# PT08ttl2.net
KiCad netlist of a schematic drawn in EAGLE
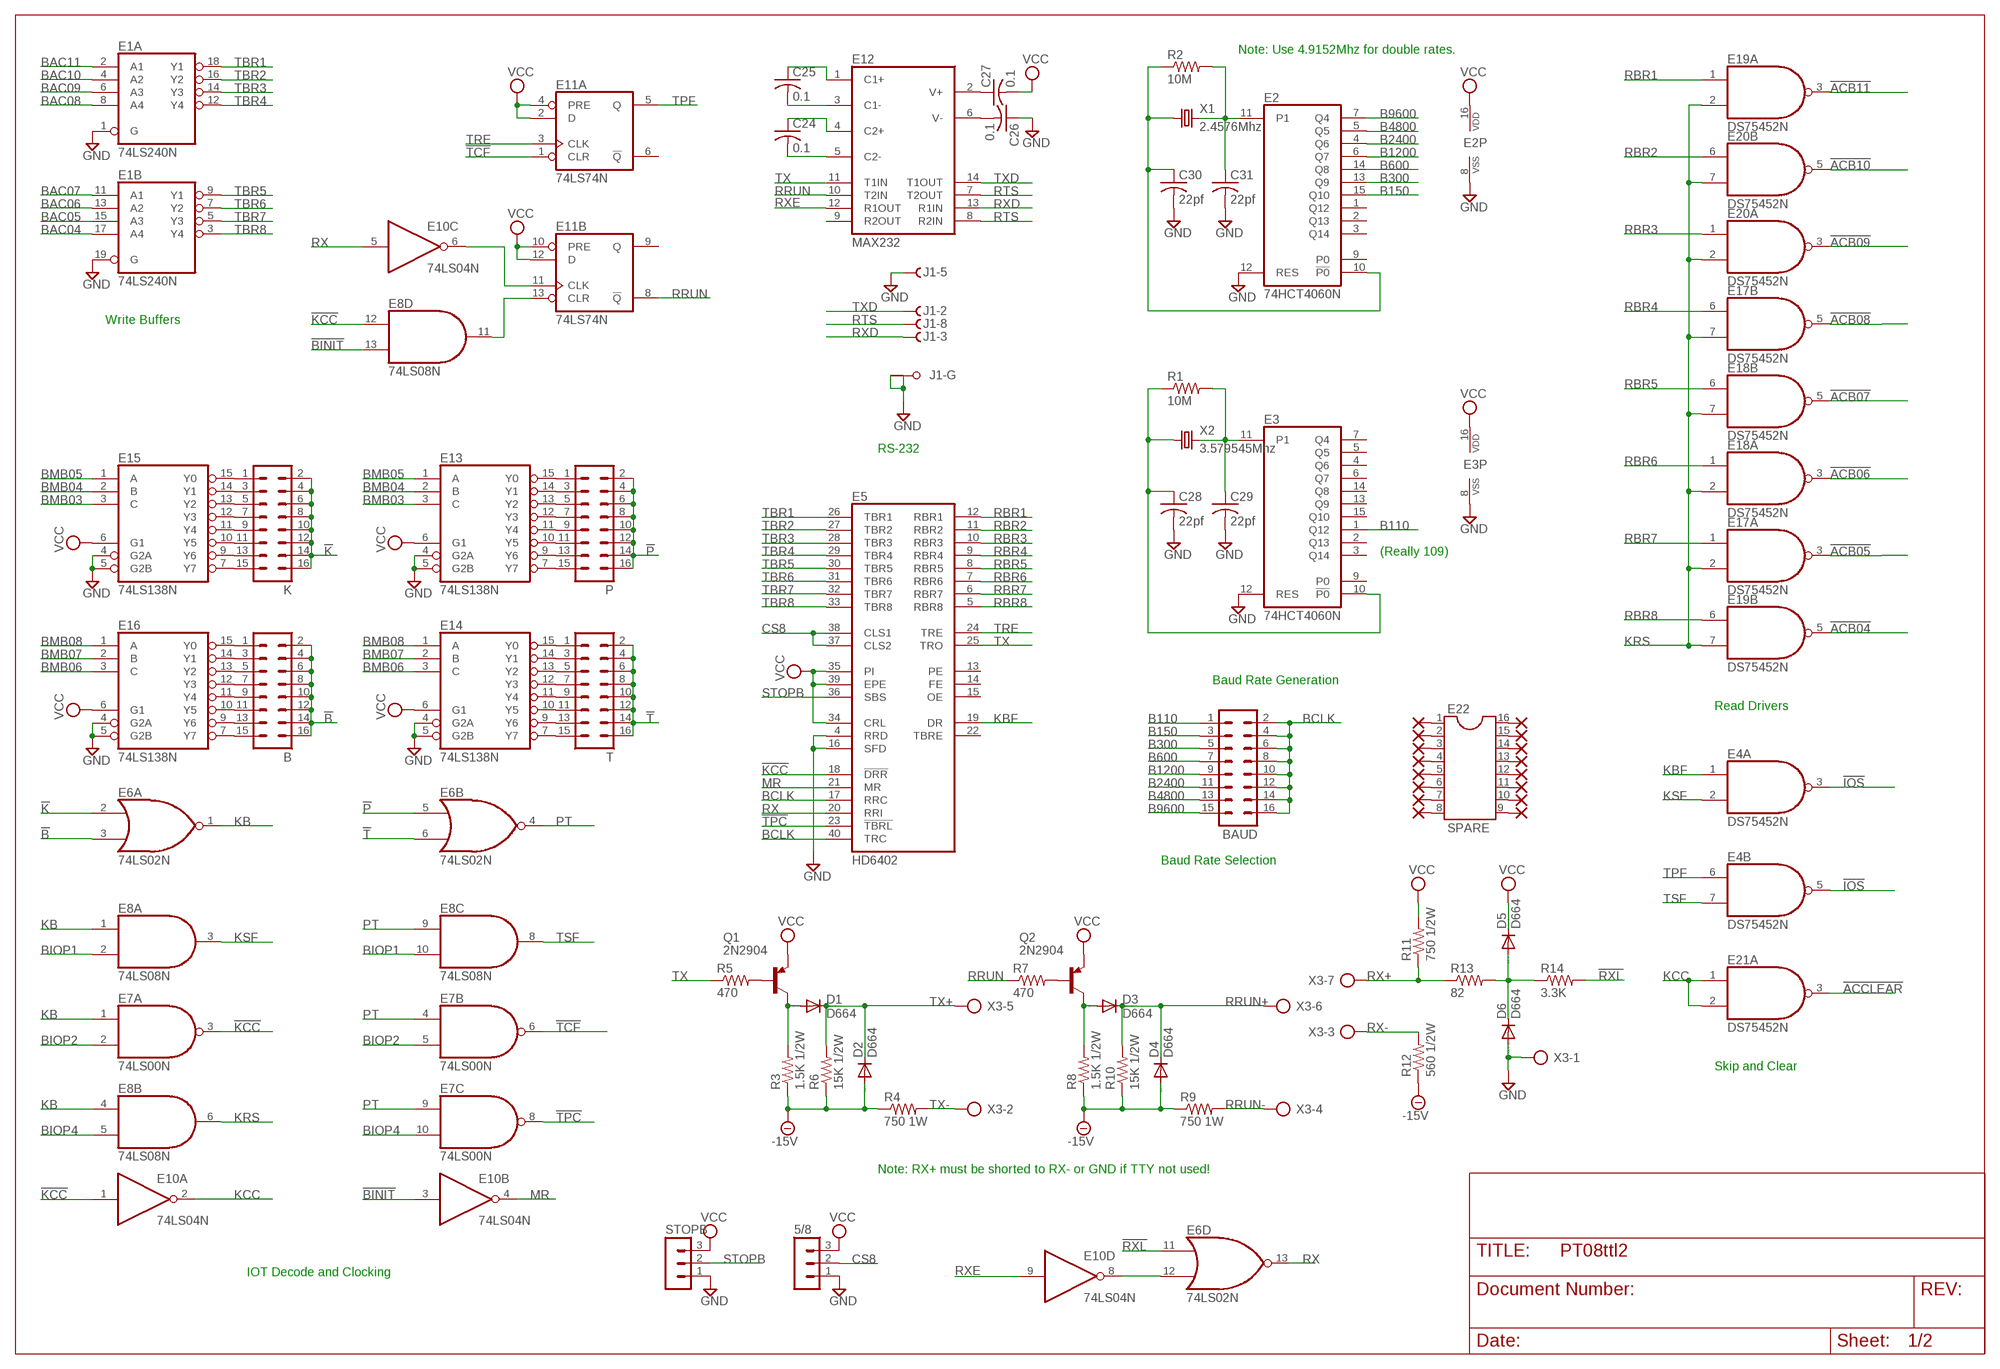
[diagram p0: schematic, sheet 1]
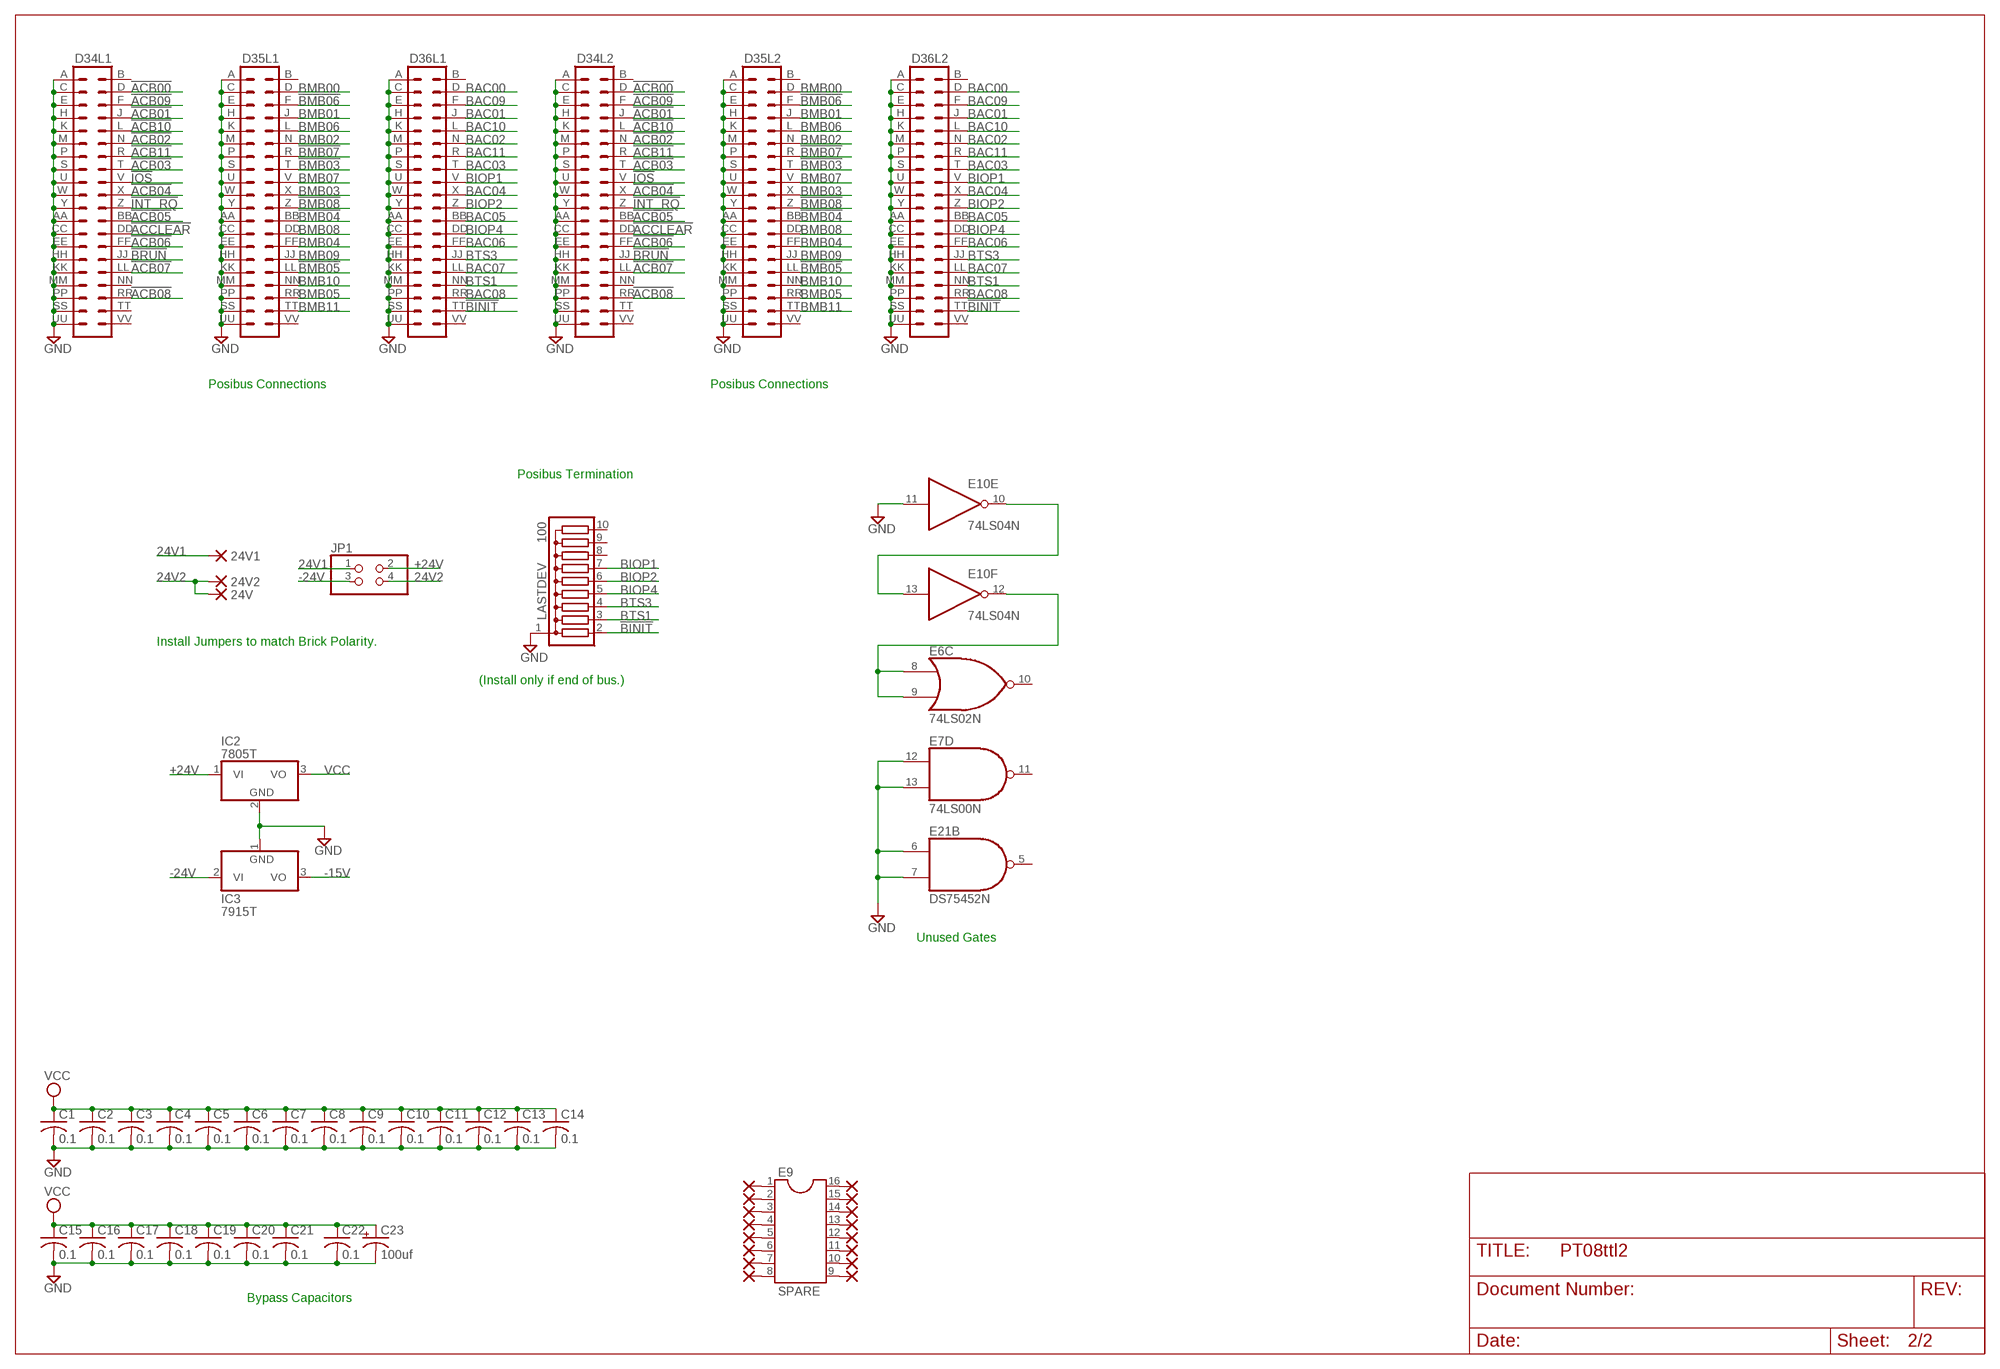
[diagram p1: schematic, sheet 2]

(export (version "E")
  (design (tool "Eeschema 10.0.6"))
  (components
    (comp (ref "5/8")
      (value "MA03-1")
      (footprint "eagle-import:MA03-1")
      (libsource (lib "eagle-import") (part "MA03-1"))
    )
    (comp (ref "B")
      (value "MA08-2")
      (footprint "eagle-import:MA08-2")
      (libsource (lib "eagle-import") (part "MA08-2"))
    )
    (comp (ref "BAUD")
      (value "MA08-2")
      (footprint "eagle-import:MA08-2")
      (libsource (lib "eagle-import") (part "MA08-2"))
    )
    (comp (ref "C24")
      (value "0.1")
      (footprint "eagle-import:C050-025X075")
      (libsource (lib "eagle-import") (part "C-US050-025X075"))
    )
    (comp (ref "C25")
      (value "0.1")
      (footprint "eagle-import:C050-025X075")
      (libsource (lib "eagle-import") (part "C-US050-025X075"))
    )
    (comp (ref "C26")
      (value "0.1")
      (footprint "eagle-import:C050-025X075")
      (libsource (lib "eagle-import") (part "C-US050-025X075"))
    )
    (comp (ref "C27")
      (value "0.1")
      (footprint "eagle-import:C050-025X075")
      (libsource (lib "eagle-import") (part "C-US050-025X075"))
    )
    (comp (ref "C28")
      (value "22pf")
      (footprint "eagle-import:C050-025X075")
      (libsource (lib "eagle-import") (part "C-US050-025X075"))
    )
    (comp (ref "C29")
      (value "22pf")
      (footprint "eagle-import:C050-025X075")
      (libsource (lib "eagle-import") (part "C-US050-025X075"))
    )
    (comp (ref "C30")
      (value "22pf")
      (footprint "eagle-import:C050-025X075")
      (libsource (lib "eagle-import") (part "C-US050-025X075"))
    )
    (comp (ref "C31")
      (value "22pf")
      (footprint "eagle-import:C050-025X075")
      (libsource (lib "eagle-import") (part "C-US050-025X075"))
    )
    (comp (ref "D1")
      (value "D664")
      (footprint "eagle-import:DO35-10")
      (libsource (lib "eagle-import") (part "1N4148DO35-10"))
    )
    (comp (ref "D2")
      (value "D664")
      (footprint "eagle-import:DO35-10")
      (libsource (lib "eagle-import") (part "1N4148DO35-10"))
    )
    (comp (ref "D3")
      (value "D664")
      (footprint "eagle-import:DO35-10")
      (libsource (lib "eagle-import") (part "1N4148DO35-10"))
    )
    (comp (ref "D4")
      (value "D664")
      (footprint "eagle-import:DO35-10")
      (libsource (lib "eagle-import") (part "1N4148DO35-10"))
    )
    (comp (ref "D5")
      (value "D664")
      (footprint "eagle-import:DO35-10")
      (libsource (lib "eagle-import") (part "1N4148DO35-10"))
    )
    (comp (ref "D6")
      (value "D664")
      (footprint "eagle-import:DO35-10")
      (libsource (lib "eagle-import") (part "1N4148DO35-10"))
    )
    (comp (ref "E1")
      (value "74LS240N")
      (footprint "eagle-import:DIL20")
      (libsource (lib "eagle-import") (part "74240NLS"))
    )
    (comp (ref "E2")
      (value "74HCT4060N")
      (footprint "eagle-import:DIL16")
      (libsource (lib "eagle-import") (part "4060N"))
    )
    (comp (ref "E3")
      (value "74HCT4060N")
      (footprint "eagle-import:DIL16")
      (libsource (lib "eagle-import") (part "4060N"))
    )
    (comp (ref "E4")
      (value "DS75452N")
      (footprint "eagle-import:DIL08")
      (libsource (lib "eagle-import") (part "DS75452N"))
    )
    (comp (ref "E5")
      (value "HD6402")
      (footprint "eagle-import:DIL40")
      (libsource (lib "eagle-import") (part "HD6402"))
    )
    (comp (ref "E6")
      (value "74LS02N")
      (footprint "eagle-import:DIL14")
      (libsource (lib "eagle-import") (part "7402NLS"))
    )
    (comp (ref "E7")
      (value "74LS00N")
      (footprint "eagle-import:DIL14")
      (libsource (lib "eagle-import") (part "7400NLS"))
    )
    (comp (ref "E8")
      (value "74LS08N")
      (footprint "eagle-import:DIL14")
      (libsource (lib "eagle-import") (part "7408NLS"))
    )
    (comp (ref "E10")
      (value "74LS04N")
      (footprint "eagle-import:DIL14")
      (libsource (lib "eagle-import") (part "7404NLS"))
    )
    (comp (ref "E11")
      (value "74LS74N")
      (footprint "eagle-import:DIL14")
      (libsource (lib "eagle-import") (part "7474NLS"))
    )
    (comp (ref "E12")
      (value "MAX232")
      (footprint "eagle-import:DIL16")
      (fields (field (name "MF") "MAXIM") (field (name "MPN") "MAX232ACPE+"))
      (libsource (lib "eagle-import") (part "MAX232"))
    )
    (comp (ref "E13")
      (value "74LS138N")
      (footprint "eagle-import:DIL16")
      (libsource (lib "eagle-import") (part "74138NLS"))
    )
    (comp (ref "E14")
      (value "74LS138N")
      (footprint "eagle-import:DIL16")
      (libsource (lib "eagle-import") (part "74138NLS"))
    )
    (comp (ref "E15")
      (value "74LS138N")
      (footprint "eagle-import:DIL16")
      (libsource (lib "eagle-import") (part "74138NLS"))
    )
    (comp (ref "E16")
      (value "74LS138N")
      (footprint "eagle-import:DIL16")
      (libsource (lib "eagle-import") (part "74138NLS"))
    )
    (comp (ref "E17")
      (value "DS75452N")
      (footprint "eagle-import:DIL08")
      (libsource (lib "eagle-import") (part "DS75452N"))
    )
    (comp (ref "E18")
      (value "DS75452N")
      (footprint "eagle-import:DIL08")
      (libsource (lib "eagle-import") (part "DS75452N"))
    )
    (comp (ref "E19")
      (value "DS75452N")
      (footprint "eagle-import:DIL08")
      (libsource (lib "eagle-import") (part "DS75452N"))
    )
    (comp (ref "E20")
      (value "DS75452N")
      (footprint "eagle-import:DIL08")
      (libsource (lib "eagle-import") (part "DS75452N"))
    )
    (comp (ref "E21")
      (value "DS75452N")
      (footprint "eagle-import:DIL08")
      (libsource (lib "eagle-import") (part "DS75452N"))
    )
    (comp (ref "E22")
      (value "SPARE")
      (footprint "eagle-import:DIL16")
      (libsource (lib "eagle-import") (part "DIL16"))
    )
    (comp (ref "J1")
      (value "F09HPS")
      (footprint "eagle-import:F09HP")
      (libsource (lib "eagle-import") (part "F09HPS"))
    )
    (comp (ref "K")
      (value "MA08-2")
      (footprint "eagle-import:MA08-2")
      (libsource (lib "eagle-import") (part "MA08-2"))
    )
    (comp (ref "P")
      (value "MA08-2")
      (footprint "eagle-import:MA08-2")
      (libsource (lib "eagle-import") (part "MA08-2"))
    )
    (comp (ref "PAD18")
      (value "1,6/0,8")
      (footprint "eagle-import:1,6_0,8")
      (libsource (lib "eagle-import") (part "1,6/0,8"))
    )
    (comp (ref "PAD19")
      (value "1,6/0,8")
      (footprint "eagle-import:1,6_0,8")
      (libsource (lib "eagle-import") (part "1,6/0,8"))
    )
    (comp (ref "PAD28")
      (value "1,6/0,8")
      (footprint "eagle-import:1,6_0,8")
      (libsource (lib "eagle-import") (part "1,6/0,8"))
    )
    (comp (ref "PAD29")
      (value "1,6/0,8")
      (footprint "eagle-import:1,6_0,8")
      (libsource (lib "eagle-import") (part "1,6/0,8"))
    )
    (comp (ref "PAD30")
      (value "1,6/0,8")
      (footprint "eagle-import:1,6_0,8")
      (libsource (lib "eagle-import") (part "1,6/0,8"))
    )
    (comp (ref "PAD31")
      (value "1,6/0,8")
      (footprint "eagle-import:1,6_0,8")
      (libsource (lib "eagle-import") (part "1,6/0,8"))
    )
    (comp (ref "PAD32")
      (value "1,6/0,8")
      (footprint "eagle-import:1,6_0,8")
      (libsource (lib "eagle-import") (part "1,6/0,8"))
    )
    (comp (ref "PAD33")
      (value "1,6/0,8")
      (footprint "eagle-import:1,6_0,8")
      (libsource (lib "eagle-import") (part "1,6/0,8"))
    )
    (comp (ref "PAD34")
      (value "1,6/0,8")
      (footprint "eagle-import:1,6_0,8")
      (libsource (lib "eagle-import") (part "1,6/0,8"))
    )
    (comp (ref "PAD35")
      (value "1,6/0,8")
      (footprint "eagle-import:1,6_0,8")
      (libsource (lib "eagle-import") (part "1,6/0,8"))
    )
    (comp (ref "PAD36")
      (value "1,6/0,8")
      (footprint "eagle-import:1,6_0,8")
      (libsource (lib "eagle-import") (part "1,6/0,8"))
    )
    (comp (ref "PAD37")
      (value "1,6/0,8")
      (footprint "eagle-import:1,6_0,8")
      (libsource (lib "eagle-import") (part "1,6/0,8"))
    )
    (comp (ref "PAD38")
      (value "1,6/0,8")
      (footprint "eagle-import:1,6_0,8")
      (libsource (lib "eagle-import") (part "1,6/0,8"))
    )
    (comp (ref "PAD39")
      (value "1,6/0,8")
      (footprint "eagle-import:1,6_0,8")
      (libsource (lib "eagle-import") (part "1,6/0,8"))
    )
    (comp (ref "PAD40")
      (value "1,6/0,8")
      (footprint "eagle-import:1,6_0,8")
      (libsource (lib "eagle-import") (part "1,6/0,8"))
    )
    (comp (ref "PAD41")
      (value "1,6/0,8")
      (footprint "eagle-import:1,6_0,8")
      (libsource (lib "eagle-import") (part "1,6/0,8"))
    )
    (comp (ref "Q1")
      (value "2N2904")
      (footprint "eagle-import:TO39")
      (libsource (lib "eagle-import") (part "2N2904"))
    )
    (comp (ref "Q2")
      (value "2N2904")
      (footprint "eagle-import:TO39")
      (libsource (lib "eagle-import") (part "2N2904"))
    )
    (comp (ref "R1")
      (value "10M")
      (footprint "eagle-import:0207_10")
      (libsource (lib "eagle-import") (part "R-US_0207/10"))
    )
    (comp (ref "R2")
      (value "10M")
      (footprint "eagle-import:0207_10")
      (libsource (lib "eagle-import") (part "R-US_0207/10"))
    )
    (comp (ref "R3")
      (value "1.5K 1/2W")
      (footprint "eagle-import:0207_10")
      (libsource (lib "eagle-import") (part "R-US_0207/10"))
    )
    (comp (ref "R4")
      (value "750 1W")
      (footprint "eagle-import:0207_10")
      (libsource (lib "eagle-import") (part "R-US_0207/10"))
    )
    (comp (ref "R5")
      (value "470")
      (footprint "eagle-import:0207_10")
      (libsource (lib "eagle-import") (part "R-US_0207/10"))
    )
    (comp (ref "R6")
      (value "15K 1/2W")
      (footprint "eagle-import:0207_10")
      (libsource (lib "eagle-import") (part "R-US_0207/10"))
    )
    (comp (ref "R7")
      (value "470")
      (footprint "eagle-import:0207_10")
      (libsource (lib "eagle-import") (part "R-US_0207/10"))
    )
    (comp (ref "R8")
      (value "1.5K 1/2W")
      (footprint "eagle-import:0207_10")
      (libsource (lib "eagle-import") (part "R-US_0207/10"))
    )
    (comp (ref "R9")
      (value "750 1W")
      (footprint "eagle-import:0207_10")
      (libsource (lib "eagle-import") (part "R-US_0207/10"))
    )
    (comp (ref "R10")
      (value "15K 1/2W")
      (footprint "eagle-import:0207_10")
      (libsource (lib "eagle-import") (part "R-US_0207/10"))
    )
    (comp (ref "R11")
      (value "750 1/2W")
      (footprint "eagle-import:0207_10")
      (libsource (lib "eagle-import") (part "R-US_0207/10"))
    )
    (comp (ref "R12")
      (value "560 1/2W")
      (footprint "eagle-import:0207_10")
      (libsource (lib "eagle-import") (part "R-US_0207/10"))
    )
    (comp (ref "R13")
      (value "82")
      (footprint "eagle-import:0207_10")
      (libsource (lib "eagle-import") (part "R-US_0207/10"))
    )
    (comp (ref "R14")
      (value "3.3K")
      (footprint "eagle-import:0207_10")
      (libsource (lib "eagle-import") (part "R-US_0207/10"))
    )
    (comp (ref "STOPB")
      (value "MA03-1")
      (footprint "eagle-import:MA03-1")
      (libsource (lib "eagle-import") (part "MA03-1"))
    )
    (comp (ref "T")
      (value "MA08-2")
      (footprint "eagle-import:MA08-2")
      (libsource (lib "eagle-import") (part "MA08-2"))
    )
    (comp (ref "X1")
      (value "2.4576Mhz")
      (footprint "eagle-import:HC49U-V")
      (libsource (lib "eagle-import") (part "CRYSTALHC49U-V"))
    )
    (comp (ref "X2")
      (value "3.579545Mhz")
      (footprint "eagle-import:HC49U-V")
      (libsource (lib "eagle-import") (part "CRYSTALHC49U-V"))
    )
    (comp (ref "X3")
      (value "AK300/7")
      (footprint "eagle-import:AK300_7")
      (libsource (lib "eagle-import") (part "AK300/7"))
    )
    (comp (ref "24V")
      (value "PAD-0820")
      (footprint "eagle-import:0820")
      (libsource (lib "eagle-import") (part "PAD-0820"))
    )
    (comp (ref "24V1")
      (value "PAD-0820")
      (footprint "eagle-import:0820")
      (libsource (lib "eagle-import") (part "PAD-0820"))
    )
    (comp (ref "24V2")
      (value "PAD-0820")
      (footprint "eagle-import:0820")
      (libsource (lib "eagle-import") (part "PAD-0820"))
    )
    (comp (ref "C1")
      (value "0.1")
      (footprint "eagle-import:C050-025X075")
      (libsource (lib "eagle-import") (part "C-US050-025X075"))
    )
    (comp (ref "C2")
      (value "0.1")
      (footprint "eagle-import:C050-025X075")
      (libsource (lib "eagle-import") (part "C-US050-025X075"))
    )
    (comp (ref "C3")
      (value "0.1")
      (footprint "eagle-import:C050-025X075")
      (libsource (lib "eagle-import") (part "C-US050-025X075"))
    )
    (comp (ref "C4")
      (value "0.1")
      (footprint "eagle-import:C050-025X075")
      (libsource (lib "eagle-import") (part "C-US050-025X075"))
    )
    (comp (ref "C5")
      (value "0.1")
      (footprint "eagle-import:C050-025X075")
      (libsource (lib "eagle-import") (part "C-US050-025X075"))
    )
    (comp (ref "C6")
      (value "0.1")
      (footprint "eagle-import:C050-025X075")
      (libsource (lib "eagle-import") (part "C-US050-025X075"))
    )
    (comp (ref "C7")
      (value "0.1")
      (footprint "eagle-import:C050-025X075")
      (libsource (lib "eagle-import") (part "C-US050-025X075"))
    )
    (comp (ref "C8")
      (value "0.1")
      (footprint "eagle-import:C050-025X075")
      (libsource (lib "eagle-import") (part "C-US050-025X075"))
    )
    (comp (ref "C9")
      (value "0.1")
      (footprint "eagle-import:C050-025X075")
      (libsource (lib "eagle-import") (part "C-US050-025X075"))
    )
    (comp (ref "C10")
      (value "0.1")
      (footprint "eagle-import:C050-025X075")
      (libsource (lib "eagle-import") (part "C-US050-025X075"))
    )
    (comp (ref "C11")
      (value "0.1")
      (footprint "eagle-import:C050-025X075")
      (libsource (lib "eagle-import") (part "C-US050-025X075"))
    )
    (comp (ref "C12")
      (value "0.1")
      (footprint "eagle-import:C050-025X075")
      (libsource (lib "eagle-import") (part "C-US050-025X075"))
    )
    (comp (ref "C13")
      (value "0.1")
      (footprint "eagle-import:C050-025X075")
      (libsource (lib "eagle-import") (part "C-US050-025X075"))
    )
    (comp (ref "C14")
      (value "0.1")
      (footprint "eagle-import:C050-025X075")
      (libsource (lib "eagle-import") (part "C-US050-025X075"))
    )
    (comp (ref "C15")
      (value "0.1")
      (footprint "eagle-import:C050-025X075")
      (libsource (lib "eagle-import") (part "C-US050-025X075"))
    )
    (comp (ref "C16")
      (value "0.1")
      (footprint "eagle-import:C050-025X075")
      (libsource (lib "eagle-import") (part "C-US050-025X075"))
    )
    (comp (ref "C17")
      (value "0.1")
      (footprint "eagle-import:C050-025X075")
      (libsource (lib "eagle-import") (part "C-US050-025X075"))
    )
    (comp (ref "C18")
      (value "0.1")
      (footprint "eagle-import:C050-025X075")
      (libsource (lib "eagle-import") (part "C-US050-025X075"))
    )
    (comp (ref "C19")
      (value "0.1")
      (footprint "eagle-import:C050-025X075")
      (libsource (lib "eagle-import") (part "C-US050-025X075"))
    )
    (comp (ref "C20")
      (value "0.1")
      (footprint "eagle-import:C050-025X075")
      (libsource (lib "eagle-import") (part "C-US050-025X075"))
    )
    (comp (ref "C21")
      (value "0.1")
      (footprint "eagle-import:C050-025X075")
      (libsource (lib "eagle-import") (part "C-US050-025X075"))
    )
    (comp (ref "C22")
      (value "0.1")
      (footprint "eagle-import:C050-025X075")
      (libsource (lib "eagle-import") (part "C-US050-025X075"))
    )
    (comp (ref "C23")
      (value "100uf")
      (footprint "eagle-import:E22-9")
      (libsource (lib "eagle-import") (part "CPOL-USE22-9AXIAL"))
    )
    (comp (ref "D34L1")
      (value "DEC40PINV")
      (footprint "eagle-import:DEC40PINV")
      (libsource (lib "eagle-import") (part "DEC40PINV"))
    )
    (comp (ref "D34L2")
      (value "DEC40PINV")
      (footprint "eagle-import:DEC40PINV")
      (libsource (lib "eagle-import") (part "DEC40PINV"))
    )
    (comp (ref "D35L1")
      (value "DEC40PINV")
      (footprint "eagle-import:DEC40PINV")
      (libsource (lib "eagle-import") (part "DEC40PINV"))
    )
    (comp (ref "D35L2")
      (value "DEC40PINV")
      (footprint "eagle-import:DEC40PINV")
      (libsource (lib "eagle-import") (part "DEC40PINV"))
    )
    (comp (ref "D36L1")
      (value "DEC40PINV")
      (footprint "eagle-import:DEC40PINV")
      (libsource (lib "eagle-import") (part "DEC40PINV"))
    )
    (comp (ref "D36L2")
      (value "DEC40PINV")
      (footprint "eagle-import:DEC40PINV")
      (libsource (lib "eagle-import") (part "DEC40PINV"))
    )
    (comp (ref "E9")
      (value "SPARE")
      (footprint "eagle-import:DIL16")
      (libsource (lib "eagle-import") (part "DIL16"))
    )
    (comp (ref "IC2")
      (value "7805T")
      (footprint "eagle-import:TO220H")
      (libsource (lib "eagle-import") (part "78T05"))
    )
    (comp (ref "IC3")
      (value "7915T")
      (footprint "eagle-import:TO220H")
      (libsource (lib "eagle-import") (part "79T15"))
    )
    (comp (ref "JP1")
      (value "PINHD-2X2")
      (footprint "eagle-import:2X02")
      (libsource (lib "eagle-import") (part "PINHD-2X2"))
    )
    (comp (ref "LASTDEV")
      (value "100")
      (footprint "eagle-import:SIL10")
      (libsource (lib "eagle-import") (part "G09R"))
    )
    (comp (ref "PAD1")
      (value "1,6/0,8")
      (footprint "eagle-import:1,6_0,8")
      (libsource (lib "eagle-import") (part "1,6/0,8"))
    )
    (comp (ref "PAD2")
      (value "1,6/0,8")
      (footprint "eagle-import:1,6_0,8")
      (libsource (lib "eagle-import") (part "1,6/0,8"))
    )
    (comp (ref "PAD3")
      (value "1,6/0,8")
      (footprint "eagle-import:1,6_0,8")
      (libsource (lib "eagle-import") (part "1,6/0,8"))
    )
    (comp (ref "PAD4")
      (value "1,6/0,8")
      (footprint "eagle-import:1,6_0,8")
      (libsource (lib "eagle-import") (part "1,6/0,8"))
    )
    (comp (ref "PAD5")
      (value "1,6/0,8")
      (footprint "eagle-import:1,6_0,8")
      (libsource (lib "eagle-import") (part "1,6/0,8"))
    )
    (comp (ref "PAD6")
      (value "1,6/0,8")
      (footprint "eagle-import:1,6_0,8")
      (libsource (lib "eagle-import") (part "1,6/0,8"))
    )
    (comp (ref "PAD7")
      (value "1,6/0,8")
      (footprint "eagle-import:1,6_0,8")
      (libsource (lib "eagle-import") (part "1,6/0,8"))
    )
    (comp (ref "PAD8")
      (value "1,6/0,8")
      (footprint "eagle-import:1,6_0,8")
      (libsource (lib "eagle-import") (part "1,6/0,8"))
    )
    (comp (ref "PAD9")
      (value "1,6/0,8")
      (footprint "eagle-import:1,6_0,8")
      (libsource (lib "eagle-import") (part "1,6/0,8"))
    )
    (comp (ref "PAD42")
      (value "1,6/0,8")
      (footprint "eagle-import:1,6_0,8")
      (libsource (lib "eagle-import") (part "1,6/0,8"))
    )
    (comp (ref "PAD43")
      (value "1,6/0,8")
      (footprint "eagle-import:1,6_0,8")
      (libsource (lib "eagle-import") (part "1,6/0,8"))
    )
    (comp (ref "PAD44")
      (value "1,6/0,8")
      (footprint "eagle-import:1,6_0,8")
      (libsource (lib "eagle-import") (part "1,6/0,8"))
    )
    (comp (ref "PAD45")
      (value "1,6/0,8")
      (footprint "eagle-import:1,6_0,8")
      (libsource (lib "eagle-import") (part "1,6/0,8"))
    )
    (comp (ref "PAD46")
      (value "1,6/0,8")
      (footprint "eagle-import:1,6_0,8")
      (libsource (lib "eagle-import") (part "1,6/0,8"))
    )
    (comp (ref "PAD47")
      (value "1,6/0,8")
      (footprint "eagle-import:1,6_0,8")
      (libsource (lib "eagle-import") (part "1,6/0,8"))
    )
    (comp (ref "PAD48")
      (value "1,6/0,8")
      (footprint "eagle-import:1,6_0,8")
      (libsource (lib "eagle-import") (part "1,6/0,8"))
    )
  )
  (nets
    (net (code "1") (name "+24V") (class "Default")
      (node (ref "IC2") (pin "1") (pinfunction "VI_1") (pintype "input"))
      (node (ref "JP1") (pin "2") (pinfunction "2_2") (pintype "passive"))
    )
    (net (code "2") (name "-15V") (class "Default")
      (node (ref "D2") (pin "A") (pinfunction "A_A") (pintype "passive"))
      (node (ref "D4") (pin "A") (pinfunction "A_A") (pintype "passive"))
      (node (ref "IC3") (pin "3") (pinfunction "VO_3") (pintype "passive"))
      (node (ref "R10") (pin "1") (pinfunction "1_1") (pintype "passive"))
      (node (ref "R12") (pin "1") (pinfunction "1_1") (pintype "passive"))
      (node (ref "R3") (pin "1") (pinfunction "1_1") (pintype "passive"))
      (node (ref "R4") (pin "1") (pinfunction "1_1") (pintype "passive"))
      (node (ref "R6") (pin "1") (pinfunction "1_1") (pintype "passive"))
      (node (ref "R8") (pin "1") (pinfunction "1_1") (pintype "passive"))
      (node (ref "R9") (pin "1") (pinfunction "1_1") (pintype "passive"))
    )
    (net (code "3") (name "-24V") (class "Default")
      (node (ref "IC3") (pin "2") (pinfunction "VI_2") (pintype "input"))
      (node (ref "JP1") (pin "3") (pinfunction "3_3") (pintype "passive"))
    )
    (net (code "4") (name "24V1") (class "Default")
      (node (ref "24V1") (pin "P$1") (pinfunction "P_P$1") (pintype "passive"))
      (node (ref "JP1") (pin "1") (pinfunction "1_1") (pintype "passive"))
    )
    (net (code "5") (name "24V2") (class "Default")
      (node (ref "24V") (pin "P$1") (pinfunction "P_P$1") (pintype "passive"))
      (node (ref "24V2") (pin "P$1") (pinfunction "P_P$1") (pintype "passive"))
      (node (ref "JP1") (pin "4") (pinfunction "4_4") (pintype "passive"))
    )
    (net (code "6") (name "B110") (class "Default")
      (node (ref "BAUD") (pin "1") (pinfunction "1_1") (pintype "passive"))
      (node (ref "E3") (pin "1") (pinfunction "Q12_1") (pintype "output"))
    )
    (net (code "7") (name "B150") (class "Default")
      (node (ref "BAUD") (pin "3") (pinfunction "3_3") (pintype "passive"))
      (node (ref "E2") (pin "15") (pinfunction "Q10_15") (pintype "output"))
    )
    (net (code "8") (name "B300") (class "Default")
      (node (ref "BAUD") (pin "5") (pinfunction "5_5") (pintype "passive"))
      (node (ref "E2") (pin "13") (pinfunction "Q9_13") (pintype "output"))
    )
    (net (code "9") (name "B600") (class "Default")
      (node (ref "BAUD") (pin "7") (pinfunction "7_7") (pintype "passive"))
      (node (ref "E2") (pin "14") (pinfunction "Q8_14") (pintype "output"))
    )
    (net (code "10") (name "B1200") (class "Default")
      (node (ref "BAUD") (pin "9") (pinfunction "9_9") (pintype "passive"))
      (node (ref "E2") (pin "6") (pinfunction "Q7_6") (pintype "output"))
    )
    (net (code "11") (name "B2400") (class "Default")
      (node (ref "BAUD") (pin "11") (pinfunction "11_11") (pintype "passive"))
      (node (ref "E2") (pin "4") (pinfunction "Q6_4") (pintype "output"))
    )
    (net (code "12") (name "B4800") (class "Default")
      (node (ref "BAUD") (pin "13") (pinfunction "13_13") (pintype "passive"))
      (node (ref "E2") (pin "5") (pinfunction "Q5_5") (pintype "output"))
    )
    (net (code "13") (name "B9600") (class "Default")
      (node (ref "BAUD") (pin "15") (pinfunction "15_15") (pintype "passive"))
      (node (ref "E2") (pin "7") (pinfunction "Q4_7") (pintype "output"))
    )
    (net (code "14") (name "BAC00") (class "Default")
      (node (ref "D36L1") (pin "D") (pinfunction "4_D") (pintype "bidirectional"))
      (node (ref "D36L2") (pin "D") (pinfunction "4_D") (pintype "bidirectional"))
    )
    (net (code "15") (name "BAC01") (class "Default")
      (node (ref "D36L1") (pin "J") (pinfunction "8_J") (pintype "bidirectional"))
      (node (ref "D36L2") (pin "J") (pinfunction "8_J") (pintype "bidirectional"))
    )
    (net (code "16") (name "BAC02") (class "Default")
      (node (ref "D36L1") (pin "N") (pinfunction "12_N") (pintype "bidirectional"))
      (node (ref "D36L2") (pin "N") (pinfunction "12_N") (pintype "bidirectional"))
    )
    (net (code "17") (name "BAC03") (class "Default")
      (node (ref "D36L1") (pin "T") (pinfunction "16_T") (pintype "bidirectional"))
      (node (ref "D36L2") (pin "T") (pinfunction "16_T") (pintype "bidirectional"))
    )
    (net (code "18") (name "BAC04") (class "Default")
      (node (ref "D36L1") (pin "X") (pinfunction "20_X") (pintype "bidirectional"))
      (node (ref "D36L2") (pin "X") (pinfunction "20_X") (pintype "bidirectional"))
      (node (ref "E1") (pin "17") (pinfunction "A4_17") (pintype "input"))
    )
    (net (code "19") (name "BAC05") (class "Default")
      (node (ref "D36L1") (pin "BB") (pinfunction "24_BB") (pintype "bidirectional"))
      (node (ref "D36L2") (pin "BB") (pinfunction "24_BB") (pintype "bidirectional"))
      (node (ref "E1") (pin "15") (pinfunction "A3_15") (pintype "input"))
    )
    (net (code "20") (name "BAC06") (class "Default")
      (node (ref "D36L1") (pin "FF") (pinfunction "28_FF") (pintype "bidirectional"))
      (node (ref "D36L2") (pin "FF") (pinfunction "28_FF") (pintype "bidirectional"))
      (node (ref "E1") (pin "13") (pinfunction "A2_13") (pintype "input"))
    )
    (net (code "21") (name "BAC07") (class "Default")
      (node (ref "D36L1") (pin "LL") (pinfunction "32_LL") (pintype "bidirectional"))
      (node (ref "D36L2") (pin "LL") (pinfunction "32_LL") (pintype "bidirectional"))
      (node (ref "E1") (pin "11") (pinfunction "A1_11") (pintype "input"))
    )
    (net (code "22") (name "BAC08") (class "Default")
      (node (ref "D36L1") (pin "RR") (pinfunction "36_RR") (pintype "bidirectional"))
      (node (ref "D36L2") (pin "RR") (pinfunction "36_RR") (pintype "bidirectional"))
      (node (ref "E1") (pin "8") (pinfunction "A4_8") (pintype "input"))
    )
    (net (code "23") (name "BAC09") (class "Default")
      (node (ref "D36L1") (pin "F") (pinfunction "6_F") (pintype "bidirectional"))
      (node (ref "D36L2") (pin "F") (pinfunction "6_F") (pintype "bidirectional"))
      (node (ref "E1") (pin "6") (pinfunction "A3_6") (pintype "input"))
    )
    (net (code "24") (name "BAC10") (class "Default")
      (node (ref "D36L1") (pin "L") (pinfunction "10_L") (pintype "bidirectional"))
      (node (ref "D36L2") (pin "L") (pinfunction "10_L") (pintype "bidirectional"))
      (node (ref "E1") (pin "4") (pinfunction "A2_4") (pintype "input"))
    )
    (net (code "25") (name "BAC11") (class "Default")
      (node (ref "D36L1") (pin "R") (pinfunction "14_R") (pintype "bidirectional"))
      (node (ref "D36L2") (pin "R") (pinfunction "14_R") (pintype "bidirectional"))
      (node (ref "E1") (pin "2") (pinfunction "A1_2") (pintype "input"))
    )
    (net (code "26") (name "BCLK") (class "Default")
      (node (ref "BAUD") (pin "10") (pinfunction "10_10") (pintype "passive"))
      (node (ref "BAUD") (pin "12") (pinfunction "12_12") (pintype "passive"))
      (node (ref "BAUD") (pin "14") (pinfunction "14_14") (pintype "passive"))
      (node (ref "BAUD") (pin "16") (pinfunction "16_16") (pintype "passive"))
      (node (ref "BAUD") (pin "2") (pinfunction "2_2") (pintype "passive"))
      (node (ref "BAUD") (pin "4") (pinfunction "4_4") (pintype "passive"))
      (node (ref "BAUD") (pin "6") (pinfunction "6_6") (pintype "passive"))
      (node (ref "BAUD") (pin "8") (pinfunction "8_8") (pintype "passive"))
      (node (ref "E5") (pin "17") (pinfunction "RRC_17") (pintype "input"))
      (node (ref "E5") (pin "40") (pinfunction "TRC_40") (pintype "input"))
    )
    (net (code "27") (name "BIOP1") (class "Default")
      (node (ref "D36L1") (pin "V") (pinfunction "18_V") (pintype "bidirectional"))
      (node (ref "D36L2") (pin "V") (pinfunction "18_V") (pintype "bidirectional"))
      (node (ref "E8") (pin "10") (pinfunction "I1_10") (pintype "input"))
      (node (ref "E8") (pin "2") (pinfunction "I1_2") (pintype "input"))
      (node (ref "LASTDEV") (pin "7") (pinfunction "7_7") (pintype "passive"))
    )
    (net (code "28") (name "BIOP2") (class "Default")
      (node (ref "D36L1") (pin "Z") (pinfunction "22_Z") (pintype "bidirectional"))
      (node (ref "D36L2") (pin "Z") (pinfunction "22_Z") (pintype "bidirectional"))
      (node (ref "E7") (pin "2") (pinfunction "I1_2") (pintype "input"))
      (node (ref "E7") (pin "5") (pinfunction "I1_5") (pintype "input"))
      (node (ref "LASTDEV") (pin "6") (pinfunction "6_6") (pintype "passive"))
    )
    (net (code "29") (name "BIOP4") (class "Default")
      (node (ref "D36L1") (pin "DD") (pinfunction "26_DD") (pintype "bidirectional"))
      (node (ref "D36L2") (pin "DD") (pinfunction "26_DD") (pintype "bidirectional"))
      (node (ref "E7") (pin "10") (pinfunction "I1_10") (pintype "input"))
      (node (ref "E8") (pin "5") (pinfunction "I1_5") (pintype "input"))
      (node (ref "LASTDEV") (pin "5") (pinfunction "5_5") (pintype "passive"))
    )
    (net (code "30") (name "BMB00") (class "Default")
      (node (ref "D35L1") (pin "D") (pinfunction "4_D") (pintype "bidirectional"))
      (node (ref "D35L2") (pin "D") (pinfunction "4_D") (pintype "bidirectional"))
    )
    (net (code "31") (name "BMB01") (class "Default")
      (node (ref "D35L1") (pin "J") (pinfunction "8_J") (pintype "bidirectional"))
      (node (ref "D35L2") (pin "J") (pinfunction "8_J") (pintype "bidirectional"))
    )
    (net (code "32") (name "BMB02") (class "Default")
      (node (ref "D35L1") (pin "N") (pinfunction "12_N") (pintype "bidirectional"))
      (node (ref "D35L2") (pin "N") (pinfunction "12_N") (pintype "bidirectional"))
    )
    (net (code "33") (name "BMB03") (class "Default")
      (node (ref "D35L1") (pin "X") (pinfunction "20_X") (pintype "bidirectional"))
      (node (ref "D35L2") (pin "X") (pinfunction "20_X") (pintype "bidirectional"))
      (node (ref "E13") (pin "3") (pinfunction "C_3") (pintype "input"))
      (node (ref "E15") (pin "3") (pinfunction "C_3") (pintype "input"))
    )
    (net (code "34") (name "BMB04") (class "Default")
      (node (ref "D35L1") (pin "FF") (pinfunction "28_FF") (pintype "bidirectional"))
      (node (ref "D35L2") (pin "FF") (pinfunction "28_FF") (pintype "bidirectional"))
      (node (ref "E13") (pin "2") (pinfunction "B_2") (pintype "input"))
      (node (ref "E15") (pin "2") (pinfunction "B_2") (pintype "input"))
    )
    (net (code "35") (name "BMB05") (class "Default")
      (node (ref "D35L1") (pin "RR") (pinfunction "36_RR") (pintype "bidirectional"))
      (node (ref "D35L2") (pin "RR") (pinfunction "36_RR") (pintype "bidirectional"))
      (node (ref "E13") (pin "1") (pinfunction "A_1") (pintype "input"))
      (node (ref "E15") (pin "1") (pinfunction "A_1") (pintype "input"))
    )
    (net (code "36") (name "BMB06") (class "Default")
      (node (ref "D35L1") (pin "L") (pinfunction "10_L") (pintype "bidirectional"))
      (node (ref "D35L2") (pin "L") (pinfunction "10_L") (pintype "bidirectional"))
      (node (ref "E14") (pin "3") (pinfunction "C_3") (pintype "input"))
      (node (ref "E16") (pin "3") (pinfunction "C_3") (pintype "input"))
    )
    (net (code "37") (name "BMB07") (class "Default")
      (node (ref "D35L1") (pin "V") (pinfunction "18_V") (pintype "bidirectional"))
      (node (ref "D35L2") (pin "V") (pinfunction "18_V") (pintype "bidirectional"))
      (node (ref "E14") (pin "2") (pinfunction "B_2") (pintype "input"))
      (node (ref "E16") (pin "2") (pinfunction "B_2") (pintype "input"))
    )
    (net (code "38") (name "BMB08") (class "Default")
      (node (ref "D35L1") (pin "DD") (pinfunction "26_DD") (pintype "bidirectional"))
      (node (ref "D35L2") (pin "DD") (pinfunction "26_DD") (pintype "bidirectional"))
      (node (ref "E14") (pin "1") (pinfunction "A_1") (pintype "input"))
      (node (ref "E16") (pin "1") (pinfunction "A_1") (pintype "input"))
    )
    (net (code "39") (name "BMB09") (class "Default")
      (node (ref "D35L1") (pin "JJ") (pinfunction "30_JJ") (pintype "bidirectional"))
      (node (ref "D35L2") (pin "JJ") (pinfunction "30_JJ") (pintype "bidirectional"))
    )
    (net (code "40") (name "BMB10") (class "Default")
      (node (ref "D35L1") (pin "NN") (pinfunction "34_NN") (pintype "bidirectional"))
      (node (ref "D35L2") (pin "NN") (pinfunction "34_NN") (pintype "bidirectional"))
    )
    (net (code "41") (name "BMB11") (class "Default")
      (node (ref "D35L1") (pin "TT") (pinfunction "38_TT") (pintype "bidirectional"))
      (node (ref "D35L2") (pin "TT") (pinfunction "38_TT") (pintype "bidirectional"))
    )
    (net (code "42") (name "BTS1") (class "Default")
      (node (ref "D36L1") (pin "NN") (pinfunction "34_NN") (pintype "bidirectional"))
      (node (ref "D36L2") (pin "NN") (pinfunction "34_NN") (pintype "bidirectional"))
      (node (ref "LASTDEV") (pin "3") (pinfunction "3_3") (pintype "passive"))
    )
    (net (code "43") (name "BTS3") (class "Default")
      (node (ref "D36L1") (pin "JJ") (pinfunction "30_JJ") (pintype "bidirectional"))
      (node (ref "D36L2") (pin "JJ") (pinfunction "30_JJ") (pintype "bidirectional"))
      (node (ref "LASTDEV") (pin "4") (pinfunction "4_4") (pintype "passive"))
    )
    (net (code "44") (name "CS8") (class "Default")
      (node (ref "5/8") (pin "2") (pinfunction "2_2") (pintype "passive"))
      (node (ref "E5") (pin "37") (pinfunction "CLS2_37") (pintype "input"))
      (node (ref "E5") (pin "38") (pinfunction "CLS1_38") (pintype "input"))
    )
    (net (code "45") (name "GND") (class "Default")
      (node (ref "5/8") (pin "1") (pinfunction "1_1") (pintype "passive"))
      (node (ref "C1") (pin "2") (pinfunction "2_2") (pintype "passive"))
      (node (ref "C10") (pin "2") (pinfunction "2_2") (pintype "passive"))
      (node (ref "C11") (pin "2") (pinfunction "2_2") (pintype "passive"))
      (node (ref "C12") (pin "2") (pinfunction "2_2") (pintype "passive"))
      (node (ref "C13") (pin "2") (pinfunction "2_2") (pintype "passive"))
      (node (ref "C14") (pin "2") (pinfunction "2_2") (pintype "passive"))
      (node (ref "C15") (pin "2") (pinfunction "2_2") (pintype "passive"))
      (node (ref "C16") (pin "2") (pinfunction "2_2") (pintype "passive"))
      (node (ref "C17") (pin "2") (pinfunction "2_2") (pintype "passive"))
      (node (ref "C18") (pin "2") (pinfunction "2_2") (pintype "passive"))
      (node (ref "C19") (pin "2") (pinfunction "2_2") (pintype "passive"))
      (node (ref "C2") (pin "2") (pinfunction "2_2") (pintype "passive"))
      (node (ref "C20") (pin "2") (pinfunction "2_2") (pintype "passive"))
      (node (ref "C21") (pin "2") (pinfunction "2_2") (pintype "passive"))
      (node (ref "C22") (pin "2") (pinfunction "2_2") (pintype "passive"))
      (node (ref "C23") (pin "-") (pinfunction "-_-") (pintype "passive"))
      (node (ref "C26") (pin "1") (pinfunction "1_1") (pintype "passive"))
      (node (ref "C28") (pin "2") (pinfunction "2_2") (pintype "passive"))
      (node (ref "C29") (pin "2") (pinfunction "2_2") (pintype "passive"))
      (node (ref "C3") (pin "2") (pinfunction "2_2") (pintype "passive"))
      (node (ref "C30") (pin "2") (pinfunction "2_2") (pintype "passive"))
      (node (ref "C31") (pin "2") (pinfunction "2_2") (pintype "passive"))
      (node (ref "C4") (pin "2") (pinfunction "2_2") (pintype "passive"))
      (node (ref "C5") (pin "2") (pinfunction "2_2") (pintype "passive"))
      (node (ref "C6") (pin "2") (pinfunction "2_2") (pintype "passive"))
      (node (ref "C7") (pin "2") (pinfunction "2_2") (pintype "passive"))
      (node (ref "C8") (pin "2") (pinfunction "2_2") (pintype "passive"))
      (node (ref "C9") (pin "2") (pinfunction "2_2") (pintype "passive"))
      (node (ref "D34L1") (pin "A") (pinfunction "1_A") (pintype "bidirectional"))
      (node (ref "D34L1") (pin "AA") (pinfunction "23_AA") (pintype "bidirectional"))
      (node (ref "D34L1") (pin "C") (pinfunction "3_C") (pintype "bidirectional"))
      (node (ref "D34L1") (pin "CC") (pinfunction "25_CC") (pintype "bidirectional"))
      (node (ref "D34L1") (pin "E") (pinfunction "5_E") (pintype "bidirectional"))
      (node (ref "D34L1") (pin "EE") (pinfunction "27_EE") (pintype "bidirectional"))
      (node (ref "D34L1") (pin "H") (pinfunction "7_H") (pintype "bidirectional"))
      (node (ref "D34L1") (pin "HH") (pinfunction "29_HH") (pintype "bidirectional"))
      (node (ref "D34L1") (pin "K") (pinfunction "9_K") (pintype "bidirectional"))
      (node (ref "D34L1") (pin "KK") (pinfunction "31_KK") (pintype "bidirectional"))
      (node (ref "D34L1") (pin "M") (pinfunction "11_M") (pintype "bidirectional"))
      (node (ref "D34L1") (pin "MM") (pinfunction "33_MM") (pintype "bidirectional"))
      (node (ref "D34L1") (pin "P") (pinfunction "13_P") (pintype "bidirectional"))
      (node (ref "D34L1") (pin "PP") (pinfunction "35_PP") (pintype "bidirectional"))
      (node (ref "D34L1") (pin "S") (pinfunction "15_S") (pintype "bidirectional"))
      (node (ref "D34L1") (pin "SS") (pinfunction "37_SS") (pintype "bidirectional"))
      (node (ref "D34L1") (pin "U") (pinfunction "17_U") (pintype "bidirectional"))
      (node (ref "D34L1") (pin "UU") (pinfunction "39_UU") (pintype "bidirectional"))
      (node (ref "D34L1") (pin "W") (pinfunction "19_W") (pintype "bidirectional"))
      (node (ref "D34L1") (pin "Y") (pinfunction "21_Y") (pintype "bidirectional"))
      (node (ref "D34L2") (pin "A") (pinfunction "1_A") (pintype "bidirectional"))
      (node (ref "D34L2") (pin "AA") (pinfunction "23_AA") (pintype "bidirectional"))
      (node (ref "D34L2") (pin "C") (pinfunction "3_C") (pintype "bidirectional"))
      (node (ref "D34L2") (pin "CC") (pinfunction "25_CC") (pintype "bidirectional"))
      (node (ref "D34L2") (pin "E") (pinfunction "5_E") (pintype "bidirectional"))
      (node (ref "D34L2") (pin "EE") (pinfunction "27_EE") (pintype "bidirectional"))
      (node (ref "D34L2") (pin "H") (pinfunction "7_H") (pintype "bidirectional"))
      (node (ref "D34L2") (pin "HH") (pinfunction "29_HH") (pintype "bidirectional"))
      (node (ref "D34L2") (pin "K") (pinfunction "9_K") (pintype "bidirectional"))
      (node (ref "D34L2") (pin "KK") (pinfunction "31_KK") (pintype "bidirectional"))
      (node (ref "D34L2") (pin "M") (pinfunction "11_M") (pintype "bidirectional"))
      (node (ref "D34L2") (pin "MM") (pinfunction "33_MM") (pintype "bidirectional"))
      (node (ref "D34L2") (pin "P") (pinfunction "13_P") (pintype "bidirectional"))
      (node (ref "D34L2") (pin "PP") (pinfunction "35_PP") (pintype "bidirectional"))
      (node (ref "D34L2") (pin "S") (pinfunction "15_S") (pintype "bidirectional"))
      (node (ref "D34L2") (pin "SS") (pinfunction "37_SS") (pintype "bidirectional"))
      (node (ref "D34L2") (pin "U") (pinfunction "17_U") (pintype "bidirectional"))
      (node (ref "D34L2") (pin "UU") (pinfunction "39_UU") (pintype "bidirectional"))
      (node (ref "D34L2") (pin "W") (pinfunction "19_W") (pintype "bidirectional"))
      (node (ref "D34L2") (pin "Y") (pinfunction "21_Y") (pintype "bidirectional"))
      (node (ref "D35L1") (pin "A") (pinfunction "1_A") (pintype "bidirectional"))
      (node (ref "D35L1") (pin "AA") (pinfunction "23_AA") (pintype "bidirectional"))
      (node (ref "D35L1") (pin "C") (pinfunction "3_C") (pintype "bidirectional"))
      (node (ref "D35L1") (pin "CC") (pinfunction "25_CC") (pintype "bidirectional"))
      (node (ref "D35L1") (pin "E") (pinfunction "5_E") (pintype "bidirectional"))
      (node (ref "D35L1") (pin "EE") (pinfunction "27_EE") (pintype "bidirectional"))
      (node (ref "D35L1") (pin "H") (pinfunction "7_H") (pintype "bidirectional"))
      (node (ref "D35L1") (pin "HH") (pinfunction "29_HH") (pintype "bidirectional"))
      (node (ref "D35L1") (pin "K") (pinfunction "9_K") (pintype "bidirectional"))
      (node (ref "D35L1") (pin "KK") (pinfunction "31_KK") (pintype "bidirectional"))
      (node (ref "D35L1") (pin "M") (pinfunction "11_M") (pintype "bidirectional"))
      (node (ref "D35L1") (pin "MM") (pinfunction "33_MM") (pintype "bidirectional"))
      (node (ref "D35L1") (pin "P") (pinfunction "13_P") (pintype "bidirectional"))
      (node (ref "D35L1") (pin "PP") (pinfunction "35_PP") (pintype "bidirectional"))
      (node (ref "D35L1") (pin "S") (pinfunction "15_S") (pintype "bidirectional"))
      (node (ref "D35L1") (pin "SS") (pinfunction "37_SS") (pintype "bidirectional"))
      (node (ref "D35L1") (pin "U") (pinfunction "17_U") (pintype "bidirectional"))
      (node (ref "D35L1") (pin "UU") (pinfunction "39_UU") (pintype "bidirectional"))
      (node (ref "D35L1") (pin "W") (pinfunction "19_W") (pintype "bidirectional"))
      (node (ref "D35L1") (pin "Y") (pinfunction "21_Y") (pintype "bidirectional"))
      (node (ref "D35L2") (pin "A") (pinfunction "1_A") (pintype "bidirectional"))
      (node (ref "D35L2") (pin "AA") (pinfunction "23_AA") (pintype "bidirectional"))
      (node (ref "D35L2") (pin "C") (pinfunction "3_C") (pintype "bidirectional"))
      (node (ref "D35L2") (pin "CC") (pinfunction "25_CC") (pintype "bidirectional"))
      (node (ref "D35L2") (pin "E") (pinfunction "5_E") (pintype "bidirectional"))
      (node (ref "D35L2") (pin "EE") (pinfunction "27_EE") (pintype "bidirectional"))
      (node (ref "D35L2") (pin "H") (pinfunction "7_H") (pintype "bidirectional"))
      (node (ref "D35L2") (pin "HH") (pinfunction "29_HH") (pintype "bidirectional"))
      (node (ref "D35L2") (pin "K") (pinfunction "9_K") (pintype "bidirectional"))
      (node (ref "D35L2") (pin "KK") (pinfunction "31_KK") (pintype "bidirectional"))
      (node (ref "D35L2") (pin "M") (pinfunction "11_M") (pintype "bidirectional"))
      (node (ref "D35L2") (pin "MM") (pinfunction "33_MM") (pintype "bidirectional"))
      (node (ref "D35L2") (pin "P") (pinfunction "13_P") (pintype "bidirectional"))
      (node (ref "D35L2") (pin "PP") (pinfunction "35_PP") (pintype "bidirectional"))
      (node (ref "D35L2") (pin "S") (pinfunction "15_S") (pintype "bidirectional"))
      (node (ref "D35L2") (pin "SS") (pinfunction "37_SS") (pintype "bidirectional"))
      (node (ref "D35L2") (pin "U") (pinfunction "17_U") (pintype "bidirectional"))
      (node (ref "D35L2") (pin "UU") (pinfunction "39_UU") (pintype "bidirectional"))
      (node (ref "D35L2") (pin "W") (pinfunction "19_W") (pintype "bidirectional"))
      (node (ref "D35L2") (pin "Y") (pinfunction "21_Y") (pintype "bidirectional"))
      (node (ref "D36L1") (pin "A") (pinfunction "1_A") (pintype "bidirectional"))
      (node (ref "D36L1") (pin "AA") (pinfunction "23_AA") (pintype "bidirectional"))
      (node (ref "D36L1") (pin "C") (pinfunction "3_C") (pintype "bidirectional"))
      (node (ref "D36L1") (pin "CC") (pinfunction "25_CC") (pintype "bidirectional"))
      (node (ref "D36L1") (pin "E") (pinfunction "5_E") (pintype "bidirectional"))
      (node (ref "D36L1") (pin "EE") (pinfunction "27_EE") (pintype "bidirectional"))
      (node (ref "D36L1") (pin "H") (pinfunction "7_H") (pintype "bidirectional"))
      (node (ref "D36L1") (pin "HH") (pinfunction "29_HH") (pintype "bidirectional"))
      (node (ref "D36L1") (pin "K") (pinfunction "9_K") (pintype "bidirectional"))
      (node (ref "D36L1") (pin "KK") (pinfunction "31_KK") (pintype "bidirectional"))
      (node (ref "D36L1") (pin "M") (pinfunction "11_M") (pintype "bidirectional"))
      (node (ref "D36L1") (pin "MM") (pinfunction "33_MM") (pintype "bidirectional"))
      (node (ref "D36L1") (pin "P") (pinfunction "13_P") (pintype "bidirectional"))
      (node (ref "D36L1") (pin "PP") (pinfunction "35_PP") (pintype "bidirectional"))
      (node (ref "D36L1") (pin "S") (pinfunction "15_S") (pintype "bidirectional"))
      (node (ref "D36L1") (pin "SS") (pinfunction "37_SS") (pintype "bidirectional"))
      (node (ref "D36L1") (pin "U") (pinfunction "17_U") (pintype "bidirectional"))
      (node (ref "D36L1") (pin "UU") (pinfunction "39_UU") (pintype "bidirectional"))
      (node (ref "D36L1") (pin "W") (pinfunction "19_W") (pintype "bidirectional"))
      (node (ref "D36L1") (pin "Y") (pinfunction "21_Y") (pintype "bidirectional"))
      (node (ref "D36L2") (pin "A") (pinfunction "1_A") (pintype "bidirectional"))
      (node (ref "D36L2") (pin "AA") (pinfunction "23_AA") (pintype "bidirectional"))
      (node (ref "D36L2") (pin "C") (pinfunction "3_C") (pintype "bidirectional"))
      (node (ref "D36L2") (pin "CC") (pinfunction "25_CC") (pintype "bidirectional"))
      (node (ref "D36L2") (pin "E") (pinfunction "5_E") (pintype "bidirectional"))
      (node (ref "D36L2") (pin "EE") (pinfunction "27_EE") (pintype "bidirectional"))
      (node (ref "D36L2") (pin "H") (pinfunction "7_H") (pintype "bidirectional"))
      (node (ref "D36L2") (pin "HH") (pinfunction "29_HH") (pintype "bidirectional"))
      (node (ref "D36L2") (pin "K") (pinfunction "9_K") (pintype "bidirectional"))
      (node (ref "D36L2") (pin "KK") (pinfunction "31_KK") (pintype "bidirectional"))
      (node (ref "D36L2") (pin "M") (pinfunction "11_M") (pintype "bidirectional"))
      (node (ref "D36L2") (pin "MM") (pinfunction "33_MM") (pintype "bidirectional"))
      (node (ref "D36L2") (pin "P") (pinfunction "13_P") (pintype "bidirectional"))
      (node (ref "D36L2") (pin "PP") (pinfunction "35_PP") (pintype "bidirectional"))
      (node (ref "D36L2") (pin "S") (pinfunction "15_S") (pintype "bidirectional"))
      (node (ref "D36L2") (pin "SS") (pinfunction "37_SS") (pintype "bidirectional"))
      (node (ref "D36L2") (pin "U") (pinfunction "17_U") (pintype "bidirectional"))
      (node (ref "D36L2") (pin "UU") (pinfunction "39_UU") (pintype "bidirectional"))
      (node (ref "D36L2") (pin "W") (pinfunction "19_W") (pintype "bidirectional"))
      (node (ref "D36L2") (pin "Y") (pinfunction "21_Y") (pintype "bidirectional"))
      (node (ref "D6") (pin "A") (pinfunction "A_A") (pintype "passive"))
      (node (ref "E1") (pin "1") (pinfunction "G_1") (pintype "input"))
      (node (ref "E1") (pin "19") (pinfunction "G_19") (pintype "input"))
      (node (ref "E10") (pin "11") (pinfunction "I_11") (pintype "input"))
      (node (ref "E13") (pin "4") (pinfunction "G2A_4") (pintype "input"))
      (node (ref "E13") (pin "5") (pinfunction "G2B_5") (pintype "input"))
      (node (ref "E14") (pin "4") (pinfunction "G2A_4") (pintype "input"))
      (node (ref "E14") (pin "5") (pinfunction "G2B_5") (pintype "input"))
      (node (ref "E15") (pin "4") (pinfunction "G2A_4") (pintype "input"))
      (node (ref "E15") (pin "5") (pinfunction "G2B_5") (pintype "input"))
      (node (ref "E16") (pin "4") (pinfunction "G2A_4") (pintype "input"))
      (node (ref "E16") (pin "5") (pinfunction "G2B_5") (pintype "input"))
      (node (ref "E2") (pin "12") (pinfunction "RES_12") (pintype "input"))
      (node (ref "E2") (pin "8") (pinfunction "VSS_8") (pintype "power_in"))
      (node (ref "E21") (pin "6") (pinfunction "I0_6") (pintype "input"))
      (node (ref "E21") (pin "7") (pinfunction "I1_7") (pintype "input"))
      (node (ref "E3") (pin "12") (pinfunction "RES_12") (pintype "input"))
      (node (ref "E3") (pin "8") (pinfunction "VSS_8") (pintype "power_in"))
      (node (ref "E5") (pin "16") (pinfunction "SFD_16") (pintype "input"))
      (node (ref "E5") (pin "4") (pinfunction "RRD_4") (pintype "input"))
      (node (ref "E7") (pin "12") (pinfunction "I0_12") (pintype "input"))
      (node (ref "E7") (pin "13") (pinfunction "I1_13") (pintype "input"))
      (node (ref "IC2") (pin "2") (pinfunction "GND_2") (pintype "passive"))
      (node (ref "IC3") (pin "1") (pinfunction "GND_1") (pintype "passive"))
      (node (ref "J1") (pin "5") (pinfunction "F_5") (pintype "passive"))
      (node (ref "J1") (pin "G1") (pinfunction "G1_G1") (pintype "passive"))
      (node (ref "J1") (pin "G2") (pinfunction "G2_G2") (pintype "passive"))
      (node (ref "LASTDEV") (pin "1") (pinfunction "1_1") (pintype "passive"))
      (node (ref "STOPB") (pin "1") (pinfunction "1_1") (pintype "passive"))
      (node (ref "X3") (pin "1") (pinfunction "KL_1") (pintype "passive"))
    )
    (net (code "46") (name "KB") (class "Default")
      (node (ref "E6") (pin "1") (pinfunction "O_1") (pintype "output"))
      (node (ref "E7") (pin "1") (pinfunction "I0_1") (pintype "input"))
      (node (ref "E8") (pin "1") (pinfunction "I0_1") (pintype "input"))
      (node (ref "E8") (pin "4") (pinfunction "I0_4") (pintype "input"))
    )
    (net (code "47") (name "KBF") (class "Default")
      (node (ref "E4") (pin "1") (pinfunction "I0_1") (pintype "input"))
      (node (ref "E5") (pin "19") (pinfunction "DR_19") (pintype "tri_state"))
    )
    (net (code "48") (name "KCC") (class "Default")
      (node (ref "E10") (pin "2") (pinfunction "O_2") (pintype "output"))
      (node (ref "E21") (pin "1") (pinfunction "I0_1") (pintype "input"))
      (node (ref "E21") (pin "2") (pinfunction "I1_2") (pintype "input"))
    )
    (net (code "49") (name "KRS") (class "Default")
      (node (ref "E17") (pin "2") (pinfunction "I1_2") (pintype "input"))
      (node (ref "E17") (pin "7") (pinfunction "I1_7") (pintype "input"))
      (node (ref "E18") (pin "2") (pinfunction "I1_2") (pintype "input"))
      (node (ref "E18") (pin "7") (pinfunction "I1_7") (pintype "input"))
      (node (ref "E19") (pin "2") (pinfunction "I1_2") (pintype "input"))
      (node (ref "E19") (pin "7") (pinfunction "I1_7") (pintype "input"))
      (node (ref "E20") (pin "2") (pinfunction "I1_2") (pintype "input"))
      (node (ref "E20") (pin "7") (pinfunction "I1_7") (pintype "input"))
      (node (ref "E8") (pin "6") (pinfunction "O_6") (pintype "output"))
    )
    (net (code "50") (name "KSF") (class "Default")
      (node (ref "E4") (pin "2") (pinfunction "I1_2") (pintype "input"))
      (node (ref "E8") (pin "3") (pinfunction "O_3") (pintype "output"))
    )
    (net (code "51") (name "MR") (class "Default")
      (node (ref "E10") (pin "4") (pinfunction "O_4") (pintype "output"))
      (node (ref "E5") (pin "21") (pinfunction "MR_21") (pintype "input"))
    )
    (net (code "52") (name "Net-(D5-PadA)") (class "Default")
      (node (ref "D5") (pin "A") (pinfunction "A_A") (pintype "passive"))
      (node (ref "D6") (pin "C") (pinfunction "C_C") (pintype "passive"))
      (node (ref "R13") (pin "2") (pinfunction "2_2") (pintype "passive"))
      (node (ref "R14") (pin "1") (pinfunction "1_1") (pintype "passive"))
    )
    (net (code "53") (name "Net-(E2A-P1)") (class "Default")
      (node (ref "C31") (pin "1") (pinfunction "1_1") (pintype "passive"))
      (node (ref "E2") (pin "11") (pinfunction "P1_11") (pintype "input"))
      (node (ref "R2") (pin "2") (pinfunction "2_2") (pintype "passive"))
      (node (ref "X1") (pin "2") (pinfunction "2_2") (pintype "passive"))
    )
    (net (code "54") (name "Net-(E2A-~{P0})") (class "Default")
      (node (ref "C30") (pin "1") (pinfunction "1_1") (pintype "passive"))
      (node (ref "E2") (pin "10") (pinfunction "~{P0}_10") (pintype "output"))
      (node (ref "R2") (pin "1") (pinfunction "1_1") (pintype "passive"))
      (node (ref "X1") (pin "1") (pinfunction "1_1") (pintype "passive"))
    )
    (net (code "55") (name "Net-(E3A-P1)") (class "Default")
      (node (ref "C29") (pin "1") (pinfunction "1_1") (pintype "passive"))
      (node (ref "E3") (pin "11") (pinfunction "P1_11") (pintype "input"))
      (node (ref "R1") (pin "2") (pinfunction "2_2") (pintype "passive"))
      (node (ref "X2") (pin "2") (pinfunction "2_2") (pintype "passive"))
    )
    (net (code "56") (name "Net-(E3A-~{P0})") (class "Default")
      (node (ref "C28") (pin "1") (pinfunction "1_1") (pintype "passive"))
      (node (ref "E3") (pin "10") (pinfunction "~{P0}_10") (pintype "output"))
      (node (ref "R1") (pin "1") (pinfunction "1_1") (pintype "passive"))
      (node (ref "X2") (pin "1") (pinfunction "1_1") (pintype "passive"))
    )
    (net (code "57") (name "Net-(E10C-O)") (class "Default")
      (node (ref "E10") (pin "6") (pinfunction "O_6") (pintype "output"))
      (node (ref "E11") (pin "11") (pinfunction "CLK_11") (pintype "input"))
    )
    (net (code "58") (name "Net-(E10D-O)") (class "Default")
      (node (ref "E10") (pin "8") (pinfunction "O_8") (pintype "output"))
      (node (ref "E6") (pin "12") (pinfunction "I1_12") (pintype "input"))
    )
    (net (code "59") (name "Net-(E10E-O)") (class "Default")
      (node (ref "E10") (pin "10") (pinfunction "O_10") (pintype "output"))
      (node (ref "E10") (pin "13") (pinfunction "I_13") (pintype "input"))
    )
    (net (code "60") (name "Net-(E10F-O)") (class "Default")
      (node (ref "E10") (pin "12") (pinfunction "O_12") (pintype "output"))
      (node (ref "E6") (pin "8") (pinfunction "I0_8") (pintype "input"))
      (node (ref "E6") (pin "9") (pinfunction "I1_9") (pintype "input"))
    )
    (net (code "61") (name "Net-(E11B-CLR)") (class "Default")
      (node (ref "E11") (pin "13") (pinfunction "CLR_13") (pintype "input"))
      (node (ref "E8") (pin "11") (pinfunction "O_11") (pintype "output"))
    )
    (net (code "62") (name "Net-(E12A-C1+)") (class "Default")
      (node (ref "C25") (pin "1") (pinfunction "1_1") (pintype "passive"))
      (node (ref "E12") (pin "1") (pinfunction "C1+_1") (pintype "bidirectional"))
    )
    (net (code "63") (name "Net-(E12A-C1-)") (class "Default")
      (node (ref "C25") (pin "2") (pinfunction "2_2") (pintype "passive"))
      (node (ref "E12") (pin "3") (pinfunction "C1-_3") (pintype "bidirectional"))
    )
    (net (code "64") (name "Net-(E12A-C2+)") (class "Default")
      (node (ref "C24") (pin "1") (pinfunction "1_1") (pintype "passive"))
      (node (ref "E12") (pin "4") (pinfunction "C2+_4") (pintype "bidirectional"))
    )
    (net (code "65") (name "Net-(E12A-C2-)") (class "Default")
      (node (ref "C24") (pin "2") (pinfunction "2_2") (pintype "passive"))
      (node (ref "E12") (pin "5") (pinfunction "C2-_5") (pintype "bidirectional"))
    )
    (net (code "66") (name "Net-(E12A-V+)") (class "Default")
      (node (ref "C27") (pin "1") (pinfunction "1_1") (pintype "passive"))
      (node (ref "E12") (pin "2") (pinfunction "V+_2") (pintype "bidirectional"))
    )
    (net (code "67") (name "Net-(E12A-V-)") (class "Default")
      (node (ref "C26") (pin "2") (pinfunction "2_2") (pintype "passive"))
      (node (ref "E12") (pin "6") (pinfunction "V-_6") (pintype "bidirectional"))
    )
    (net (code "68") (name "Net-(E13A-Y0)") (class "Default")
      (node (ref "E13") (pin "15") (pinfunction "Y0_15") (pintype "output"))
      (node (ref "P") (pin "1") (pinfunction "1_1") (pintype "passive"))
    )
    (net (code "69") (name "Net-(E13A-Y1)") (class "Default")
      (node (ref "E13") (pin "14") (pinfunction "Y1_14") (pintype "output"))
      (node (ref "P") (pin "3") (pinfunction "3_3") (pintype "passive"))
    )
    (net (code "70") (name "Net-(E13A-Y2)") (class "Default")
      (node (ref "E13") (pin "13") (pinfunction "Y2_13") (pintype "output"))
      (node (ref "P") (pin "5") (pinfunction "5_5") (pintype "passive"))
    )
    (net (code "71") (name "Net-(E13A-Y3)") (class "Default")
      (node (ref "E13") (pin "12") (pinfunction "Y3_12") (pintype "output"))
      (node (ref "P") (pin "7") (pinfunction "7_7") (pintype "passive"))
    )
    (net (code "72") (name "Net-(E13A-Y4)") (class "Default")
      (node (ref "E13") (pin "11") (pinfunction "Y4_11") (pintype "output"))
      (node (ref "P") (pin "9") (pinfunction "9_9") (pintype "passive"))
    )
    (net (code "73") (name "Net-(E13A-Y5)") (class "Default")
      (node (ref "E13") (pin "10") (pinfunction "Y5_10") (pintype "output"))
      (node (ref "P") (pin "11") (pinfunction "11_11") (pintype "passive"))
    )
    (net (code "74") (name "Net-(E13A-Y6)") (class "Default")
      (node (ref "E13") (pin "9") (pinfunction "Y6_9") (pintype "output"))
      (node (ref "P") (pin "13") (pinfunction "13_13") (pintype "passive"))
    )
    (net (code "75") (name "Net-(E13A-Y7)") (class "Default")
      (node (ref "E13") (pin "7") (pinfunction "Y7_7") (pintype "output"))
      (node (ref "P") (pin "15") (pinfunction "15_15") (pintype "passive"))
    )
    (net (code "76") (name "Net-(E14A-Y0)") (class "Default")
      (node (ref "E14") (pin "15") (pinfunction "Y0_15") (pintype "output"))
      (node (ref "T") (pin "1") (pinfunction "1_1") (pintype "passive"))
    )
    (net (code "77") (name "Net-(E14A-Y1)") (class "Default")
      (node (ref "E14") (pin "14") (pinfunction "Y1_14") (pintype "output"))
      (node (ref "T") (pin "3") (pinfunction "3_3") (pintype "passive"))
    )
    (net (code "78") (name "Net-(E14A-Y2)") (class "Default")
      (node (ref "E14") (pin "13") (pinfunction "Y2_13") (pintype "output"))
      (node (ref "T") (pin "5") (pinfunction "5_5") (pintype "passive"))
    )
    (net (code "79") (name "Net-(E14A-Y3)") (class "Default")
      (node (ref "E14") (pin "12") (pinfunction "Y3_12") (pintype "output"))
      (node (ref "T") (pin "7") (pinfunction "7_7") (pintype "passive"))
    )
    (net (code "80") (name "Net-(E14A-Y4)") (class "Default")
      (node (ref "E14") (pin "11") (pinfunction "Y4_11") (pintype "output"))
      (node (ref "T") (pin "9") (pinfunction "9_9") (pintype "passive"))
    )
    (net (code "81") (name "Net-(E14A-Y5)") (class "Default")
      (node (ref "E14") (pin "10") (pinfunction "Y5_10") (pintype "output"))
      (node (ref "T") (pin "11") (pinfunction "11_11") (pintype "passive"))
    )
    (net (code "82") (name "Net-(E14A-Y6)") (class "Default")
      (node (ref "E14") (pin "9") (pinfunction "Y6_9") (pintype "output"))
      (node (ref "T") (pin "13") (pinfunction "13_13") (pintype "passive"))
    )
    (net (code "83") (name "Net-(E14A-Y7)") (class "Default")
      (node (ref "E14") (pin "7") (pinfunction "Y7_7") (pintype "output"))
      (node (ref "T") (pin "15") (pinfunction "15_15") (pintype "passive"))
    )
    (net (code "84") (name "Net-(E15A-Y0)") (class "Default")
      (node (ref "E15") (pin "15") (pinfunction "Y0_15") (pintype "output"))
      (node (ref "K") (pin "1") (pinfunction "1_1") (pintype "passive"))
    )
    (net (code "85") (name "Net-(E15A-Y1)") (class "Default")
      (node (ref "E15") (pin "14") (pinfunction "Y1_14") (pintype "output"))
      (node (ref "K") (pin "3") (pinfunction "3_3") (pintype "passive"))
    )
    (net (code "86") (name "Net-(E15A-Y2)") (class "Default")
      (node (ref "E15") (pin "13") (pinfunction "Y2_13") (pintype "output"))
      (node (ref "K") (pin "5") (pinfunction "5_5") (pintype "passive"))
    )
    (net (code "87") (name "Net-(E15A-Y3)") (class "Default")
      (node (ref "E15") (pin "12") (pinfunction "Y3_12") (pintype "output"))
      (node (ref "K") (pin "7") (pinfunction "7_7") (pintype "passive"))
    )
    (net (code "88") (name "Net-(E15A-Y4)") (class "Default")
      (node (ref "E15") (pin "11") (pinfunction "Y4_11") (pintype "output"))
      (node (ref "K") (pin "9") (pinfunction "9_9") (pintype "passive"))
    )
    (net (code "89") (name "Net-(E15A-Y5)") (class "Default")
      (node (ref "E15") (pin "10") (pinfunction "Y5_10") (pintype "output"))
      (node (ref "K") (pin "11") (pinfunction "11_11") (pintype "passive"))
    )
    (net (code "90") (name "Net-(E15A-Y6)") (class "Default")
      (node (ref "E15") (pin "9") (pinfunction "Y6_9") (pintype "output"))
      (node (ref "K") (pin "13") (pinfunction "13_13") (pintype "passive"))
    )
    (net (code "91") (name "Net-(E15A-Y7)") (class "Default")
      (node (ref "E15") (pin "7") (pinfunction "Y7_7") (pintype "output"))
      (node (ref "K") (pin "15") (pinfunction "15_15") (pintype "passive"))
    )
    (net (code "92") (name "Net-(E16A-Y0)") (class "Default")
      (node (ref "B") (pin "1") (pinfunction "1_1") (pintype "passive"))
      (node (ref "E16") (pin "15") (pinfunction "Y0_15") (pintype "output"))
    )
    (net (code "93") (name "Net-(E16A-Y1)") (class "Default")
      (node (ref "B") (pin "3") (pinfunction "3_3") (pintype "passive"))
      (node (ref "E16") (pin "14") (pinfunction "Y1_14") (pintype "output"))
    )
    (net (code "94") (name "Net-(E16A-Y2)") (class "Default")
      (node (ref "B") (pin "5") (pinfunction "5_5") (pintype "passive"))
      (node (ref "E16") (pin "13") (pinfunction "Y2_13") (pintype "output"))
    )
    (net (code "95") (name "Net-(E16A-Y3)") (class "Default")
      (node (ref "B") (pin "7") (pinfunction "7_7") (pintype "passive"))
      (node (ref "E16") (pin "12") (pinfunction "Y3_12") (pintype "output"))
    )
    (net (code "96") (name "Net-(E16A-Y4)") (class "Default")
      (node (ref "B") (pin "9") (pinfunction "9_9") (pintype "passive"))
      (node (ref "E16") (pin "11") (pinfunction "Y4_11") (pintype "output"))
    )
    (net (code "97") (name "Net-(E16A-Y5)") (class "Default")
      (node (ref "B") (pin "11") (pinfunction "11_11") (pintype "passive"))
      (node (ref "E16") (pin "10") (pinfunction "Y5_10") (pintype "output"))
    )
    (net (code "98") (name "Net-(E16A-Y6)") (class "Default")
      (node (ref "B") (pin "13") (pinfunction "13_13") (pintype "passive"))
      (node (ref "E16") (pin "9") (pinfunction "Y6_9") (pintype "output"))
    )
    (net (code "99") (name "Net-(E16A-Y7)") (class "Default")
      (node (ref "B") (pin "15") (pinfunction "15_15") (pintype "passive"))
      (node (ref "E16") (pin "7") (pinfunction "Y7_7") (pintype "output"))
    )
    (net (code "100") (name "Net-(PAD1-P)") (class "Default")
      (node (ref "E9") (pin "1") (pinfunction "1_1") (pintype "passive"))
      (node (ref "PAD1") (pin "1") (pinfunction "P_1") (pintype "passive"))
    )
    (net (code "101") (name "Net-(PAD2-P)") (class "Default")
      (node (ref "E9") (pin "2") (pinfunction "2_2") (pintype "passive"))
      (node (ref "PAD2") (pin "1") (pinfunction "P_1") (pintype "passive"))
    )
    (net (code "102") (name "Net-(PAD3-P)") (class "Default")
      (node (ref "E9") (pin "3") (pinfunction "3_3") (pintype "passive"))
      (node (ref "PAD3") (pin "1") (pinfunction "P_1") (pintype "passive"))
    )
    (net (code "103") (name "Net-(PAD4-P)") (class "Default")
      (node (ref "E9") (pin "4") (pinfunction "4_4") (pintype "passive"))
      (node (ref "PAD4") (pin "1") (pinfunction "P_1") (pintype "passive"))
    )
    (net (code "104") (name "Net-(PAD5-P)") (class "Default")
      (node (ref "E9") (pin "5") (pinfunction "5_5") (pintype "passive"))
      (node (ref "PAD5") (pin "1") (pinfunction "P_1") (pintype "passive"))
    )
    (net (code "105") (name "Net-(PAD6-P)") (class "Default")
      (node (ref "E9") (pin "6") (pinfunction "6_6") (pintype "passive"))
      (node (ref "PAD6") (pin "1") (pinfunction "P_1") (pintype "passive"))
    )
    (net (code "106") (name "Net-(PAD7-P)") (class "Default")
      (node (ref "E9") (pin "7") (pinfunction "7_7") (pintype "passive"))
      (node (ref "PAD7") (pin "1") (pinfunction "P_1") (pintype "passive"))
    )
    (net (code "107") (name "Net-(PAD8-P)") (class "Default")
      (node (ref "E9") (pin "8") (pinfunction "8_8") (pintype "passive"))
      (node (ref "PAD8") (pin "1") (pinfunction "P_1") (pintype "passive"))
    )
    (net (code "108") (name "Net-(PAD9-P)") (class "Default")
      (node (ref "E9") (pin "16") (pinfunction "16_16") (pintype "passive"))
      (node (ref "PAD9") (pin "1") (pinfunction "P_1") (pintype "passive"))
    )
    (net (code "109") (name "Net-(PAD18-P)") (class "Default")
      (node (ref "E22") (pin "1") (pinfunction "1_1") (pintype "passive"))
      (node (ref "PAD18") (pin "1") (pinfunction "P_1") (pintype "passive"))
    )
    (net (code "110") (name "Net-(PAD19-P)") (class "Default")
      (node (ref "E22") (pin "2") (pinfunction "2_2") (pintype "passive"))
      (node (ref "PAD19") (pin "1") (pinfunction "P_1") (pintype "passive"))
    )
    (net (code "111") (name "Net-(PAD28-P)") (class "Default")
      (node (ref "E22") (pin "3") (pinfunction "3_3") (pintype "passive"))
      (node (ref "PAD28") (pin "1") (pinfunction "P_1") (pintype "passive"))
    )
    (net (code "112") (name "Net-(PAD29-P)") (class "Default")
      (node (ref "E22") (pin "4") (pinfunction "4_4") (pintype "passive"))
      (node (ref "PAD29") (pin "1") (pinfunction "P_1") (pintype "passive"))
    )
    (net (code "113") (name "Net-(PAD30-P)") (class "Default")
      (node (ref "E22") (pin "5") (pinfunction "5_5") (pintype "passive"))
      (node (ref "PAD30") (pin "1") (pinfunction "P_1") (pintype "passive"))
    )
    (net (code "114") (name "Net-(PAD31-P)") (class "Default")
      (node (ref "E22") (pin "6") (pinfunction "6_6") (pintype "passive"))
      (node (ref "PAD31") (pin "1") (pinfunction "P_1") (pintype "passive"))
    )
    (net (code "115") (name "Net-(PAD32-P)") (class "Default")
      (node (ref "E22") (pin "7") (pinfunction "7_7") (pintype "passive"))
      (node (ref "PAD32") (pin "1") (pinfunction "P_1") (pintype "passive"))
    )
    (net (code "116") (name "Net-(PAD33-P)") (class "Default")
      (node (ref "E22") (pin "8") (pinfunction "8_8") (pintype "passive"))
      (node (ref "PAD33") (pin "1") (pinfunction "P_1") (pintype "passive"))
    )
    (net (code "117") (name "Net-(PAD34-P)") (class "Default")
      (node (ref "E22") (pin "16") (pinfunction "16_16") (pintype "passive"))
      (node (ref "PAD34") (pin "1") (pinfunction "P_1") (pintype "passive"))
    )
    (net (code "118") (name "Net-(PAD35-P)") (class "Default")
      (node (ref "E22") (pin "15") (pinfunction "15_15") (pintype "passive"))
      (node (ref "PAD35") (pin "1") (pinfunction "P_1") (pintype "passive"))
    )
    (net (code "119") (name "Net-(PAD36-P)") (class "Default")
      (node (ref "E22") (pin "14") (pinfunction "14_14") (pintype "passive"))
      (node (ref "PAD36") (pin "1") (pinfunction "P_1") (pintype "passive"))
    )
    (net (code "120") (name "Net-(PAD37-P)") (class "Default")
      (node (ref "E22") (pin "13") (pinfunction "13_13") (pintype "passive"))
      (node (ref "PAD37") (pin "1") (pinfunction "P_1") (pintype "passive"))
    )
    (net (code "121") (name "Net-(PAD38-P)") (class "Default")
      (node (ref "E22") (pin "12") (pinfunction "12_12") (pintype "passive"))
      (node (ref "PAD38") (pin "1") (pinfunction "P_1") (pintype "passive"))
    )
    (net (code "122") (name "Net-(PAD39-P)") (class "Default")
      (node (ref "E22") (pin "11") (pinfunction "11_11") (pintype "passive"))
      (node (ref "PAD39") (pin "1") (pinfunction "P_1") (pintype "passive"))
    )
    (net (code "123") (name "Net-(PAD40-P)") (class "Default")
      (node (ref "E22") (pin "10") (pinfunction "10_10") (pintype "passive"))
      (node (ref "PAD40") (pin "1") (pinfunction "P_1") (pintype "passive"))
    )
    (net (code "124") (name "Net-(PAD41-P)") (class "Default")
      (node (ref "E22") (pin "9") (pinfunction "9_9") (pintype "passive"))
      (node (ref "PAD41") (pin "1") (pinfunction "P_1") (pintype "passive"))
    )
    (net (code "125") (name "Net-(PAD42-P)") (class "Default")
      (node (ref "E9") (pin "15") (pinfunction "15_15") (pintype "passive"))
      (node (ref "PAD42") (pin "1") (pinfunction "P_1") (pintype "passive"))
    )
    (net (code "126") (name "Net-(PAD43-P)") (class "Default")
      (node (ref "E9") (pin "14") (pinfunction "14_14") (pintype "passive"))
      (node (ref "PAD43") (pin "1") (pinfunction "P_1") (pintype "passive"))
    )
    (net (code "127") (name "Net-(PAD44-P)") (class "Default")
      (node (ref "E9") (pin "13") (pinfunction "13_13") (pintype "passive"))
      (node (ref "PAD44") (pin "1") (pinfunction "P_1") (pintype "passive"))
    )
    (net (code "128") (name "Net-(PAD45-P)") (class "Default")
      (node (ref "E9") (pin "12") (pinfunction "12_12") (pintype "passive"))
      (node (ref "PAD45") (pin "1") (pinfunction "P_1") (pintype "passive"))
    )
    (net (code "129") (name "Net-(PAD46-P)") (class "Default")
      (node (ref "E9") (pin "11") (pinfunction "11_11") (pintype "passive"))
      (node (ref "PAD46") (pin "1") (pinfunction "P_1") (pintype "passive"))
    )
    (net (code "130") (name "Net-(PAD47-P)") (class "Default")
      (node (ref "E9") (pin "10") (pinfunction "10_10") (pintype "passive"))
      (node (ref "PAD47") (pin "1") (pinfunction "P_1") (pintype "passive"))
    )
    (net (code "131") (name "Net-(PAD48-P)") (class "Default")
      (node (ref "E9") (pin "9") (pinfunction "9_9") (pintype "passive"))
      (node (ref "PAD48") (pin "1") (pinfunction "P_1") (pintype "passive"))
    )
    (net (code "132") (name "Net-(Q1-B)") (class "Default")
      (node (ref "Q1") (pin "2") (pinfunction "B_2") (pintype "passive"))
      (node (ref "R5") (pin "2") (pinfunction "2_2") (pintype "passive"))
    )
    (net (code "133") (name "Net-(Q1-C)") (class "Default")
      (node (ref "D1") (pin "A") (pinfunction "A_A") (pintype "passive"))
      (node (ref "Q1") (pin "3") (pinfunction "C_3") (pintype "passive"))
      (node (ref "R3") (pin "2") (pinfunction "2_2") (pintype "passive"))
    )
    (net (code "134") (name "Net-(Q2-B)") (class "Default")
      (node (ref "Q2") (pin "2") (pinfunction "B_2") (pintype "passive"))
      (node (ref "R7") (pin "2") (pinfunction "2_2") (pintype "passive"))
    )
    (net (code "135") (name "Net-(Q2-C)") (class "Default")
      (node (ref "D3") (pin "A") (pinfunction "A_A") (pintype "passive"))
      (node (ref "Q2") (pin "3") (pinfunction "C_3") (pintype "passive"))
      (node (ref "R8") (pin "2") (pinfunction "2_2") (pintype "passive"))
    )
    (net (code "136") (name "PT") (class "Default")
      (node (ref "E6") (pin "4") (pinfunction "O_4") (pintype "output"))
      (node (ref "E7") (pin "4") (pinfunction "I0_4") (pintype "input"))
      (node (ref "E7") (pin "9") (pinfunction "I0_9") (pintype "input"))
      (node (ref "E8") (pin "9") (pinfunction "I0_9") (pintype "input"))
    )
    (net (code "137") (name "RBR1") (class "Default")
      (node (ref "E19") (pin "1") (pinfunction "I0_1") (pintype "input"))
      (node (ref "E5") (pin "12") (pinfunction "RBR1_12") (pintype "tri_state"))
    )
    (net (code "138") (name "RBR2") (class "Default")
      (node (ref "E20") (pin "6") (pinfunction "I0_6") (pintype "input"))
      (node (ref "E5") (pin "11") (pinfunction "RBR2_11") (pintype "tri_state"))
    )
    (net (code "139") (name "RBR3") (class "Default")
      (node (ref "E20") (pin "1") (pinfunction "I0_1") (pintype "input"))
      (node (ref "E5") (pin "10") (pinfunction "RBR3_10") (pintype "tri_state"))
    )
    (net (code "140") (name "RBR4") (class "Default")
      (node (ref "E17") (pin "6") (pinfunction "I0_6") (pintype "input"))
      (node (ref "E5") (pin "9") (pinfunction "RBR4_9") (pintype "tri_state"))
    )
    (net (code "141") (name "RBR5") (class "Default")
      (node (ref "E18") (pin "6") (pinfunction "I0_6") (pintype "input"))
      (node (ref "E5") (pin "8") (pinfunction "RBR5_8") (pintype "tri_state"))
    )
    (net (code "142") (name "RBR6") (class "Default")
      (node (ref "E18") (pin "1") (pinfunction "I0_1") (pintype "input"))
      (node (ref "E5") (pin "7") (pinfunction "RBR6_7") (pintype "tri_state"))
    )
    (net (code "143") (name "RBR7") (class "Default")
      (node (ref "E17") (pin "1") (pinfunction "I0_1") (pintype "input"))
      (node (ref "E5") (pin "6") (pinfunction "RBR7_6") (pintype "tri_state"))
    )
    (net (code "144") (name "RBR8") (class "Default")
      (node (ref "E19") (pin "6") (pinfunction "I0_6") (pintype "input"))
      (node (ref "E5") (pin "5") (pinfunction "RBR8_5") (pintype "tri_state"))
    )
    (net (code "145") (name "RRUN") (class "Default")
      (node (ref "E11") (pin "8") (pinfunction "~{Q}_8") (pintype "output"))
      (node (ref "E12") (pin "10") (pinfunction "T2IN_10") (pintype "input"))
      (node (ref "R7") (pin "1") (pinfunction "1_1") (pintype "passive"))
    )
    (net (code "146") (name "RRUN+") (class "Default")
      (node (ref "D3") (pin "C") (pinfunction "C_C") (pintype "passive"))
      (node (ref "D4") (pin "C") (pinfunction "C_C") (pintype "passive"))
      (node (ref "R10") (pin "2") (pinfunction "2_2") (pintype "passive"))
      (node (ref "X3") (pin "6") (pinfunction "KL_6") (pintype "passive"))
    )
    (net (code "147") (name "RRUN-") (class "Default")
      (node (ref "R9") (pin "2") (pinfunction "2_2") (pintype "passive"))
      (node (ref "X3") (pin "4") (pinfunction "KL_4") (pintype "passive"))
    )
    (net (code "148") (name "RTS") (class "Default")
      (node (ref "E12") (pin "7") (pinfunction "T2OUT_7") (pintype "output"))
      (node (ref "E12") (pin "8") (pinfunction "R2IN_8") (pintype "input"))
      (node (ref "J1") (pin "8") (pinfunction "F_8") (pintype "passive"))
    )
    (net (code "149") (name "RX") (class "Default")
      (node (ref "E10") (pin "5") (pinfunction "I_5") (pintype "input"))
      (node (ref "E5") (pin "20") (pinfunction "RRI_20") (pintype "input"))
      (node (ref "E6") (pin "13") (pinfunction "O_13") (pintype "output"))
    )
    (net (code "150") (name "RX+") (class "Default")
      (node (ref "R11") (pin "1") (pinfunction "1_1") (pintype "passive"))
      (node (ref "R13") (pin "1") (pinfunction "1_1") (pintype "passive"))
      (node (ref "X3") (pin "7") (pinfunction "KL_7") (pintype "passive"))
    )
    (net (code "151") (name "RX-") (class "Default")
      (node (ref "R12") (pin "2") (pinfunction "2_2") (pintype "passive"))
      (node (ref "X3") (pin "3") (pinfunction "KL_3") (pintype "passive"))
    )
    (net (code "152") (name "RXD") (class "Default")
      (node (ref "E12") (pin "13") (pinfunction "R1IN_13") (pintype "input"))
      (node (ref "J1") (pin "3") (pinfunction "F_3") (pintype "passive"))
    )
    (net (code "153") (name "RXE") (class "Default")
      (node (ref "E10") (pin "9") (pinfunction "I_9") (pintype "input"))
      (node (ref "E12") (pin "12") (pinfunction "R1OUT_12") (pintype "output"))
    )
    (net (code "154") (name "STOPB") (class "Default")
      (node (ref "E5") (pin "36") (pinfunction "SBS_36") (pintype "input"))
      (node (ref "STOPB") (pin "2") (pinfunction "2_2") (pintype "passive"))
    )
    (net (code "155") (name "TBR1") (class "Default")
      (node (ref "E1") (pin "18") (pinfunction "Y1_18") (pintype "tri_state"))
      (node (ref "E5") (pin "26") (pinfunction "TBR1_26") (pintype "input"))
    )
    (net (code "156") (name "TBR2") (class "Default")
      (node (ref "E1") (pin "16") (pinfunction "Y2_16") (pintype "tri_state"))
      (node (ref "E5") (pin "27") (pinfunction "TBR2_27") (pintype "input"))
    )
    (net (code "157") (name "TBR3") (class "Default")
      (node (ref "E1") (pin "14") (pinfunction "Y3_14") (pintype "tri_state"))
      (node (ref "E5") (pin "28") (pinfunction "TBR3_28") (pintype "input"))
    )
    (net (code "158") (name "TBR4") (class "Default")
      (node (ref "E1") (pin "12") (pinfunction "Y4_12") (pintype "tri_state"))
      (node (ref "E5") (pin "29") (pinfunction "TBR4_29") (pintype "input"))
    )
    (net (code "159") (name "TBR5") (class "Default")
      (node (ref "E1") (pin "9") (pinfunction "Y1_9") (pintype "tri_state"))
      (node (ref "E5") (pin "30") (pinfunction "TBR5_30") (pintype "input"))
    )
    (net (code "160") (name "TBR6") (class "Default")
      (node (ref "E1") (pin "7") (pinfunction "Y2_7") (pintype "tri_state"))
      (node (ref "E5") (pin "31") (pinfunction "TBR6_31") (pintype "input"))
    )
    (net (code "161") (name "TBR7") (class "Default")
      (node (ref "E1") (pin "5") (pinfunction "Y3_5") (pintype "tri_state"))
      (node (ref "E5") (pin "32") (pinfunction "TBR7_32") (pintype "input"))
    )
    (net (code "162") (name "TBR8") (class "Default")
      (node (ref "E1") (pin "3") (pinfunction "Y4_3") (pintype "tri_state"))
      (node (ref "E5") (pin "33") (pinfunction "TBR8_33") (pintype "input"))
    )
    (net (code "163") (name "TPF") (class "Default")
      (node (ref "E11") (pin "5") (pinfunction "Q_5") (pintype "output"))
      (node (ref "E4") (pin "6") (pinfunction "I0_6") (pintype "input"))
    )
    (net (code "164") (name "TRE") (class "Default")
      (node (ref "E11") (pin "3") (pinfunction "CLK_3") (pintype "input"))
      (node (ref "E5") (pin "24") (pinfunction "TRE_24") (pintype "output"))
    )
    (net (code "165") (name "TSF") (class "Default")
      (node (ref "E4") (pin "7") (pinfunction "I1_7") (pintype "input"))
      (node (ref "E8") (pin "8") (pinfunction "O_8") (pintype "output"))
    )
    (net (code "166") (name "TX") (class "Default")
      (node (ref "E12") (pin "11") (pinfunction "T1IN_11") (pintype "input"))
      (node (ref "E5") (pin "25") (pinfunction "TRO_25") (pintype "output"))
      (node (ref "R5") (pin "1") (pinfunction "1_1") (pintype "passive"))
    )
    (net (code "167") (name "TX+") (class "Default")
      (node (ref "D1") (pin "C") (pinfunction "C_C") (pintype "passive"))
      (node (ref "D2") (pin "C") (pinfunction "C_C") (pintype "passive"))
      (node (ref "R6") (pin "2") (pinfunction "2_2") (pintype "passive"))
      (node (ref "X3") (pin "5") (pinfunction "KL_5") (pintype "passive"))
    )
    (net (code "168") (name "TX-") (class "Default")
      (node (ref "R4") (pin "2") (pinfunction "2_2") (pintype "passive"))
      (node (ref "X3") (pin "2") (pinfunction "KL_2") (pintype "passive"))
    )
    (net (code "169") (name "TXD") (class "Default")
      (node (ref "E12") (pin "14") (pinfunction "T1OUT_14") (pintype "output"))
      (node (ref "J1") (pin "2") (pinfunction "F_2") (pintype "passive"))
    )
    (net (code "170") (name "VCC") (class "Default")
      (node (ref "5/8") (pin "3") (pinfunction "3_3") (pintype "passive"))
      (node (ref "C1") (pin "1") (pinfunction "1_1") (pintype "passive"))
      (node (ref "C10") (pin "1") (pinfunction "1_1") (pintype "passive"))
      (node (ref "C11") (pin "1") (pinfunction "1_1") (pintype "passive"))
      (node (ref "C12") (pin "1") (pinfunction "1_1") (pintype "passive"))
      (node (ref "C13") (pin "1") (pinfunction "1_1") (pintype "passive"))
      (node (ref "C14") (pin "1") (pinfunction "1_1") (pintype "passive"))
      (node (ref "C15") (pin "1") (pinfunction "1_1") (pintype "passive"))
      (node (ref "C16") (pin "1") (pinfunction "1_1") (pintype "passive"))
      (node (ref "C17") (pin "1") (pinfunction "1_1") (pintype "passive"))
      (node (ref "C18") (pin "1") (pinfunction "1_1") (pintype "passive"))
      (node (ref "C19") (pin "1") (pinfunction "1_1") (pintype "passive"))
      (node (ref "C2") (pin "1") (pinfunction "1_1") (pintype "passive"))
      (node (ref "C20") (pin "1") (pinfunction "1_1") (pintype "passive"))
      (node (ref "C21") (pin "1") (pinfunction "1_1") (pintype "passive"))
      (node (ref "C22") (pin "1") (pinfunction "1_1") (pintype "passive"))
      (node (ref "C23") (pin "+") (pinfunction "+_+") (pintype "passive"))
      (node (ref "C27") (pin "2") (pinfunction "2_2") (pintype "passive"))
      (node (ref "C3") (pin "1") (pinfunction "1_1") (pintype "passive"))
      (node (ref "C4") (pin "1") (pinfunction "1_1") (pintype "passive"))
      (node (ref "C5") (pin "1") (pinfunction "1_1") (pintype "passive"))
      (node (ref "C6") (pin "1") (pinfunction "1_1") (pintype "passive"))
      (node (ref "C7") (pin "1") (pinfunction "1_1") (pintype "passive"))
      (node (ref "C8") (pin "1") (pinfunction "1_1") (pintype "passive"))
      (node (ref "C9") (pin "1") (pinfunction "1_1") (pintype "passive"))
      (node (ref "D5") (pin "C") (pinfunction "C_C") (pintype "passive"))
      (node (ref "E11") (pin "10") (pinfunction "PRE_10") (pintype "input"))
      (node (ref "E11") (pin "12") (pinfunction "D_12") (pintype "input"))
      (node (ref "E11") (pin "2") (pinfunction "D_2") (pintype "input"))
      (node (ref "E11") (pin "4") (pinfunction "PRE_4") (pintype "input"))
      (node (ref "E13") (pin "6") (pinfunction "G1_6") (pintype "input"))
      (node (ref "E14") (pin "6") (pinfunction "G1_6") (pintype "input"))
      (node (ref "E15") (pin "6") (pinfunction "G1_6") (pintype "input"))
      (node (ref "E16") (pin "6") (pinfunction "G1_6") (pintype "input"))
      (node (ref "E2") (pin "16") (pinfunction "VDD_16") (pintype "power_in"))
      (node (ref "E3") (pin "16") (pinfunction "VDD_16") (pintype "power_in"))
      (node (ref "E5") (pin "34") (pinfunction "CRL_34") (pintype "input"))
      (node (ref "E5") (pin "35") (pinfunction "PI_35") (pintype "input"))
      (node (ref "E5") (pin "39") (pinfunction "EPE_39") (pintype "input"))
      (node (ref "IC2") (pin "3") (pinfunction "VO_3") (pintype "passive"))
      (node (ref "Q1") (pin "1") (pinfunction "E_1") (pintype "passive"))
      (node (ref "Q2") (pin "1") (pinfunction "E_1") (pintype "passive"))
      (node (ref "R11") (pin "2") (pinfunction "2_2") (pintype "passive"))
      (node (ref "STOPB") (pin "3") (pinfunction "3_3") (pintype "passive"))
    )
    (net (code "171") (name "unconnected-(D34L1-2-PadB)") (class "Default")
      (node (ref "D34L1") (pin "B") (pinfunction "2_B") (pintype "bidirectional"))
    )
    (net (code "172") (name "unconnected-(D34L1-34-PadNN)") (class "Default")
      (node (ref "D34L1") (pin "NN") (pinfunction "34_NN") (pintype "bidirectional"))
    )
    (net (code "173") (name "unconnected-(D34L1-38-PadTT)") (class "Default")
      (node (ref "D34L1") (pin "TT") (pinfunction "38_TT") (pintype "bidirectional"))
    )
    (net (code "174") (name "unconnected-(D34L1-40-PadVV)") (class "Default")
      (node (ref "D34L1") (pin "VV") (pinfunction "40_VV") (pintype "bidirectional"))
    )
    (net (code "175") (name "unconnected-(D34L2-2-PadB)") (class "Default")
      (node (ref "D34L2") (pin "B") (pinfunction "2_B") (pintype "bidirectional"))
    )
    (net (code "176") (name "unconnected-(D34L2-34-PadNN)") (class "Default")
      (node (ref "D34L2") (pin "NN") (pinfunction "34_NN") (pintype "bidirectional"))
    )
    (net (code "177") (name "unconnected-(D34L2-38-PadTT)") (class "Default")
      (node (ref "D34L2") (pin "TT") (pinfunction "38_TT") (pintype "bidirectional"))
    )
    (net (code "178") (name "unconnected-(D34L2-40-PadVV)") (class "Default")
      (node (ref "D34L2") (pin "VV") (pinfunction "40_VV") (pintype "bidirectional"))
    )
    (net (code "179") (name "unconnected-(D35L1-2-PadB)") (class "Default")
      (node (ref "D35L1") (pin "B") (pinfunction "2_B") (pintype "bidirectional"))
    )
    (net (code "180") (name "unconnected-(D35L1-40-PadVV)") (class "Default")
      (node (ref "D35L1") (pin "VV") (pinfunction "40_VV") (pintype "bidirectional"))
    )
    (net (code "181") (name "unconnected-(D35L2-2-PadB)") (class "Default")
      (node (ref "D35L2") (pin "B") (pinfunction "2_B") (pintype "bidirectional"))
    )
    (net (code "182") (name "unconnected-(D35L2-40-PadVV)") (class "Default")
      (node (ref "D35L2") (pin "VV") (pinfunction "40_VV") (pintype "bidirectional"))
    )
    (net (code "183") (name "unconnected-(D36L1-2-PadB)") (class "Default")
      (node (ref "D36L1") (pin "B") (pinfunction "2_B") (pintype "bidirectional"))
    )
    (net (code "184") (name "unconnected-(D36L1-40-PadVV)") (class "Default")
      (node (ref "D36L1") (pin "VV") (pinfunction "40_VV") (pintype "bidirectional"))
    )
    (net (code "185") (name "unconnected-(D36L2-2-PadB)") (class "Default")
      (node (ref "D36L2") (pin "B") (pinfunction "2_B") (pintype "bidirectional"))
    )
    (net (code "186") (name "unconnected-(D36L2-40-PadVV)") (class "Default")
      (node (ref "D36L2") (pin "VV") (pinfunction "40_VV") (pintype "bidirectional"))
    )
    (net (code "187") (name "unconnected-(E2A-P0-Pad9)") (class "Default")
      (node (ref "E2") (pin "9") (pinfunction "P0_9") (pintype "output"))
    )
    (net (code "188") (name "unconnected-(E2A-Q12-Pad1)") (class "Default")
      (node (ref "E2") (pin "1") (pinfunction "Q12_1") (pintype "output"))
    )
    (net (code "189") (name "unconnected-(E2A-Q13-Pad2)") (class "Default")
      (node (ref "E2") (pin "2") (pinfunction "Q13_2") (pintype "output"))
    )
    (net (code "190") (name "unconnected-(E2A-Q14-Pad3)") (class "Default")
      (node (ref "E2") (pin "3") (pinfunction "Q14_3") (pintype "output"))
    )
    (net (code "191") (name "unconnected-(E3A-P0-Pad9)") (class "Default")
      (node (ref "E3") (pin "9") (pinfunction "P0_9") (pintype "output"))
    )
    (net (code "192") (name "unconnected-(E3A-Q4-Pad7)") (class "Default")
      (node (ref "E3") (pin "7") (pinfunction "Q4_7") (pintype "output"))
    )
    (net (code "193") (name "unconnected-(E3A-Q5-Pad5)") (class "Default")
      (node (ref "E3") (pin "5") (pinfunction "Q5_5") (pintype "output"))
    )
    (net (code "194") (name "unconnected-(E3A-Q6-Pad4)") (class "Default")
      (node (ref "E3") (pin "4") (pinfunction "Q6_4") (pintype "output"))
    )
    (net (code "195") (name "unconnected-(E3A-Q7-Pad6)") (class "Default")
      (node (ref "E3") (pin "6") (pinfunction "Q7_6") (pintype "output"))
    )
    (net (code "196") (name "unconnected-(E3A-Q8-Pad14)") (class "Default")
      (node (ref "E3") (pin "14") (pinfunction "Q8_14") (pintype "output"))
    )
    (net (code "197") (name "unconnected-(E3A-Q9-Pad13)") (class "Default")
      (node (ref "E3") (pin "13") (pinfunction "Q9_13") (pintype "output"))
    )
    (net (code "198") (name "unconnected-(E3A-Q10-Pad15)") (class "Default")
      (node (ref "E3") (pin "15") (pinfunction "Q10_15") (pintype "output"))
    )
    (net (code "199") (name "unconnected-(E3A-Q13-Pad2)") (class "Default")
      (node (ref "E3") (pin "2") (pinfunction "Q13_2") (pintype "output"))
    )
    (net (code "200") (name "unconnected-(E3A-Q14-Pad3)") (class "Default")
      (node (ref "E3") (pin "3") (pinfunction "Q14_3") (pintype "output"))
    )
    (net (code "201") (name "unconnected-(E5A-FE-Pad14)") (class "Default")
      (node (ref "E5") (pin "14") (pinfunction "FE_14") (pintype "tri_state"))
    )
    (net (code "202") (name "unconnected-(E5A-OE-Pad15)") (class "Default")
      (node (ref "E5") (pin "15") (pinfunction "OE_15") (pintype "tri_state"))
    )
    (net (code "203") (name "unconnected-(E5A-PE-Pad13)") (class "Default")
      (node (ref "E5") (pin "13") (pinfunction "PE_13") (pintype "tri_state"))
    )
    (net (code "204") (name "unconnected-(E5A-TBRE-Pad22)") (class "Default")
      (node (ref "E5") (pin "22") (pinfunction "TBRE_22") (pintype "tri_state"))
    )
    (net (code "205") (name "unconnected-(E6C-O-Pad10)") (class "Default")
      (node (ref "E6") (pin "10") (pinfunction "O_10") (pintype "output"))
    )
    (net (code "206") (name "unconnected-(E7D-O-Pad11)") (class "Default")
      (node (ref "E7") (pin "11") (pinfunction "O_11") (pintype "output"))
    )
    (net (code "207") (name "unconnected-(E11A-~{Q}-Pad6)") (class "Default")
      (node (ref "E11") (pin "6") (pinfunction "~{Q}_6") (pintype "output"))
    )
    (net (code "208") (name "unconnected-(E11B-Q-Pad9)") (class "Default")
      (node (ref "E11") (pin "9") (pinfunction "Q_9") (pintype "output"))
    )
    (net (code "209") (name "unconnected-(E12A-R2OUT-Pad9)") (class "Default")
      (node (ref "E12") (pin "9") (pinfunction "R2OUT_9") (pintype "output"))
    )
    (net (code "210") (name "unconnected-(E21B-O-Pad5)") (class "Default")
      (node (ref "E21") (pin "5") (pinfunction "O_5") (pintype "open_collector"))
    )
    (net (code "211") (name "unconnected-(LASTDEV-Pad8)") (class "Default")
      (node (ref "LASTDEV") (pin "8") (pinfunction "8_8") (pintype "passive"))
    )
    (net (code "212") (name "unconnected-(LASTDEV-Pad9)") (class "Default")
      (node (ref "LASTDEV") (pin "9") (pinfunction "9_9") (pintype "passive"))
    )
    (net (code "213") (name "unconnected-(LASTDEV-Pad10)") (class "Default")
      (node (ref "LASTDEV") (pin "10") (pinfunction "10_10") (pintype "passive"))
    )
    (net (code "214") (name "~{ACB00}") (class "Default")
      (node (ref "D34L1") (pin "D") (pinfunction "4_D") (pintype "bidirectional"))
      (node (ref "D34L2") (pin "D") (pinfunction "4_D") (pintype "bidirectional"))
    )
    (net (code "215") (name "~{ACB01}") (class "Default")
      (node (ref "D34L1") (pin "J") (pinfunction "8_J") (pintype "bidirectional"))
      (node (ref "D34L2") (pin "J") (pinfunction "8_J") (pintype "bidirectional"))
    )
    (net (code "216") (name "~{ACB02}") (class "Default")
      (node (ref "D34L1") (pin "N") (pinfunction "12_N") (pintype "bidirectional"))
      (node (ref "D34L2") (pin "N") (pinfunction "12_N") (pintype "bidirectional"))
    )
    (net (code "217") (name "~{ACB03}") (class "Default")
      (node (ref "D34L1") (pin "T") (pinfunction "16_T") (pintype "bidirectional"))
      (node (ref "D34L2") (pin "T") (pinfunction "16_T") (pintype "bidirectional"))
    )
    (net (code "218") (name "~{ACB04}") (class "Default")
      (node (ref "D34L1") (pin "X") (pinfunction "20_X") (pintype "bidirectional"))
      (node (ref "D34L2") (pin "X") (pinfunction "20_X") (pintype "bidirectional"))
      (node (ref "E19") (pin "5") (pinfunction "O_5") (pintype "open_collector"))
    )
    (net (code "219") (name "~{ACB05}") (class "Default")
      (node (ref "D34L1") (pin "BB") (pinfunction "24_BB") (pintype "bidirectional"))
      (node (ref "D34L2") (pin "BB") (pinfunction "24_BB") (pintype "bidirectional"))
      (node (ref "E17") (pin "3") (pinfunction "O_3") (pintype "open_collector"))
    )
    (net (code "220") (name "~{ACB06}") (class "Default")
      (node (ref "D34L1") (pin "FF") (pinfunction "28_FF") (pintype "bidirectional"))
      (node (ref "D34L2") (pin "FF") (pinfunction "28_FF") (pintype "bidirectional"))
      (node (ref "E18") (pin "3") (pinfunction "O_3") (pintype "open_collector"))
    )
    (net (code "221") (name "~{ACB07}") (class "Default")
      (node (ref "D34L1") (pin "LL") (pinfunction "32_LL") (pintype "bidirectional"))
      (node (ref "D34L2") (pin "LL") (pinfunction "32_LL") (pintype "bidirectional"))
      (node (ref "E18") (pin "5") (pinfunction "O_5") (pintype "open_collector"))
    )
    (net (code "222") (name "~{ACB08}") (class "Default")
      (node (ref "D34L1") (pin "RR") (pinfunction "36_RR") (pintype "bidirectional"))
      (node (ref "D34L2") (pin "RR") (pinfunction "36_RR") (pintype "bidirectional"))
      (node (ref "E17") (pin "5") (pinfunction "O_5") (pintype "open_collector"))
    )
    (net (code "223") (name "~{ACB09}") (class "Default")
      (node (ref "D34L1") (pin "F") (pinfunction "6_F") (pintype "bidirectional"))
      (node (ref "D34L2") (pin "F") (pinfunction "6_F") (pintype "bidirectional"))
      (node (ref "E20") (pin "3") (pinfunction "O_3") (pintype "open_collector"))
    )
    (net (code "224") (name "~{ACB10}") (class "Default")
      (node (ref "D34L1") (pin "L") (pinfunction "10_L") (pintype "bidirectional"))
      (node (ref "D34L2") (pin "L") (pinfunction "10_L") (pintype "bidirectional"))
      (node (ref "E20") (pin "5") (pinfunction "O_5") (pintype "open_collector"))
    )
    (net (code "225") (name "~{ACB11}") (class "Default")
      (node (ref "D34L1") (pin "R") (pinfunction "14_R") (pintype "bidirectional"))
      (node (ref "D34L2") (pin "R") (pinfunction "14_R") (pintype "bidirectional"))
      (node (ref "E19") (pin "3") (pinfunction "O_3") (pintype "open_collector"))
    )
    (net (code "226") (name "~{ACCLEAR}") (class "Default")
      (node (ref "D34L1") (pin "DD") (pinfunction "26_DD") (pintype "bidirectional"))
      (node (ref "D34L2") (pin "DD") (pinfunction "26_DD") (pintype "bidirectional"))
      (node (ref "E21") (pin "3") (pinfunction "O_3") (pintype "open_collector"))
    )
    (net (code "227") (name "~{BINIT}") (class "Default")
      (node (ref "D36L1") (pin "TT") (pinfunction "38_TT") (pintype "bidirectional"))
      (node (ref "D36L2") (pin "TT") (pinfunction "38_TT") (pintype "bidirectional"))
      (node (ref "E10") (pin "3") (pinfunction "I_3") (pintype "input"))
      (node (ref "E8") (pin "13") (pinfunction "I1_13") (pintype "input"))
      (node (ref "LASTDEV") (pin "2") (pinfunction "2_2") (pintype "passive"))
    )
    (net (code "228") (name "~{BMB03}") (class "Default")
      (node (ref "D35L1") (pin "T") (pinfunction "16_T") (pintype "bidirectional"))
      (node (ref "D35L2") (pin "T") (pinfunction "16_T") (pintype "bidirectional"))
    )
    (net (code "229") (name "~{BMB04}") (class "Default")
      (node (ref "D35L1") (pin "BB") (pinfunction "24_BB") (pintype "bidirectional"))
      (node (ref "D35L2") (pin "BB") (pinfunction "24_BB") (pintype "bidirectional"))
    )
    (net (code "230") (name "~{BMB05}") (class "Default")
      (node (ref "D35L1") (pin "LL") (pinfunction "32_LL") (pintype "bidirectional"))
      (node (ref "D35L2") (pin "LL") (pinfunction "32_LL") (pintype "bidirectional"))
    )
    (net (code "231") (name "~{BMB06}") (class "Default")
      (node (ref "D35L1") (pin "F") (pinfunction "6_F") (pintype "bidirectional"))
      (node (ref "D35L2") (pin "F") (pinfunction "6_F") (pintype "bidirectional"))
    )
    (net (code "232") (name "~{BMB07}") (class "Default")
      (node (ref "D35L1") (pin "R") (pinfunction "14_R") (pintype "bidirectional"))
      (node (ref "D35L2") (pin "R") (pinfunction "14_R") (pintype "bidirectional"))
    )
    (net (code "233") (name "~{BMB08}") (class "Default")
      (node (ref "D35L1") (pin "Z") (pinfunction "22_Z") (pintype "bidirectional"))
      (node (ref "D35L2") (pin "Z") (pinfunction "22_Z") (pintype "bidirectional"))
    )
    (net (code "234") (name "~{BRUN}") (class "Default")
      (node (ref "D34L1") (pin "JJ") (pinfunction "30_JJ") (pintype "bidirectional"))
      (node (ref "D34L2") (pin "JJ") (pinfunction "30_JJ") (pintype "bidirectional"))
    )
    (net (code "235") (name "~{B}") (class "Default")
      (node (ref "B") (pin "10") (pinfunction "10_10") (pintype "passive"))
      (node (ref "B") (pin "12") (pinfunction "12_12") (pintype "passive"))
      (node (ref "B") (pin "14") (pinfunction "14_14") (pintype "passive"))
      (node (ref "B") (pin "16") (pinfunction "16_16") (pintype "passive"))
      (node (ref "B") (pin "2") (pinfunction "2_2") (pintype "passive"))
      (node (ref "B") (pin "4") (pinfunction "4_4") (pintype "passive"))
      (node (ref "B") (pin "6") (pinfunction "6_6") (pintype "passive"))
      (node (ref "B") (pin "8") (pinfunction "8_8") (pintype "passive"))
      (node (ref "E6") (pin "3") (pinfunction "I1_3") (pintype "input"))
    )
    (net (code "236") (name "~{INT_RQ}") (class "Default")
      (node (ref "D34L1") (pin "Z") (pinfunction "22_Z") (pintype "bidirectional"))
      (node (ref "D34L2") (pin "Z") (pinfunction "22_Z") (pintype "bidirectional"))
    )
    (net (code "237") (name "~{IOS}") (class "Default")
      (node (ref "D34L1") (pin "V") (pinfunction "18_V") (pintype "bidirectional"))
      (node (ref "D34L2") (pin "V") (pinfunction "18_V") (pintype "bidirectional"))
      (node (ref "E4") (pin "3") (pinfunction "O_3") (pintype "open_collector"))
      (node (ref "E4") (pin "5") (pinfunction "O_5") (pintype "open_collector"))
    )
    (net (code "238") (name "~{KCC}") (class "Default")
      (node (ref "E10") (pin "1") (pinfunction "I_1") (pintype "input"))
      (node (ref "E5") (pin "18") (pinfunction "~{DRR}_18") (pintype "input"))
      (node (ref "E7") (pin "3") (pinfunction "O_3") (pintype "output"))
      (node (ref "E8") (pin "12") (pinfunction "I0_12") (pintype "input"))
    )
    (net (code "239") (name "~{K}") (class "Default")
      (node (ref "E6") (pin "2") (pinfunction "I0_2") (pintype "input"))
      (node (ref "K") (pin "10") (pinfunction "10_10") (pintype "passive"))
      (node (ref "K") (pin "12") (pinfunction "12_12") (pintype "passive"))
      (node (ref "K") (pin "14") (pinfunction "14_14") (pintype "passive"))
      (node (ref "K") (pin "16") (pinfunction "16_16") (pintype "passive"))
      (node (ref "K") (pin "2") (pinfunction "2_2") (pintype "passive"))
      (node (ref "K") (pin "4") (pinfunction "4_4") (pintype "passive"))
      (node (ref "K") (pin "6") (pinfunction "6_6") (pintype "passive"))
      (node (ref "K") (pin "8") (pinfunction "8_8") (pintype "passive"))
    )
    (net (code "240") (name "~{P}") (class "Default")
      (node (ref "E6") (pin "5") (pinfunction "I0_5") (pintype "input"))
      (node (ref "P") (pin "10") (pinfunction "10_10") (pintype "passive"))
      (node (ref "P") (pin "12") (pinfunction "12_12") (pintype "passive"))
      (node (ref "P") (pin "14") (pinfunction "14_14") (pintype "passive"))
      (node (ref "P") (pin "16") (pinfunction "16_16") (pintype "passive"))
      (node (ref "P") (pin "2") (pinfunction "2_2") (pintype "passive"))
      (node (ref "P") (pin "4") (pinfunction "4_4") (pintype "passive"))
      (node (ref "P") (pin "6") (pinfunction "6_6") (pintype "passive"))
      (node (ref "P") (pin "8") (pinfunction "8_8") (pintype "passive"))
    )
    (net (code "241") (name "~{RXL}") (class "Default")
      (node (ref "E6") (pin "11") (pinfunction "I0_11") (pintype "input"))
      (node (ref "R14") (pin "2") (pinfunction "2_2") (pintype "passive"))
    )
    (net (code "242") (name "~{TCF}") (class "Default")
      (node (ref "E11") (pin "1") (pinfunction "CLR_1") (pintype "input"))
      (node (ref "E7") (pin "6") (pinfunction "O_6") (pintype "output"))
    )
    (net (code "243") (name "~{TPC}") (class "Default")
      (node (ref "E5") (pin "23") (pinfunction "~{TBRL}_23") (pintype "input"))
      (node (ref "E7") (pin "8") (pinfunction "O_8") (pintype "output"))
    )
    (net (code "244") (name "~{T}") (class "Default")
      (node (ref "E6") (pin "6") (pinfunction "I1_6") (pintype "input"))
      (node (ref "T") (pin "10") (pinfunction "10_10") (pintype "passive"))
      (node (ref "T") (pin "12") (pinfunction "12_12") (pintype "passive"))
      (node (ref "T") (pin "14") (pinfunction "14_14") (pintype "passive"))
      (node (ref "T") (pin "16") (pinfunction "16_16") (pintype "passive"))
      (node (ref "T") (pin "2") (pinfunction "2_2") (pintype "passive"))
      (node (ref "T") (pin "4") (pinfunction "4_4") (pintype "passive"))
      (node (ref "T") (pin "6") (pinfunction "6_6") (pintype "passive"))
      (node (ref "T") (pin "8") (pinfunction "8_8") (pintype "passive"))
    )
  )
)
